# module.net
KiCad netlist of a schematic drawn in EAGLE
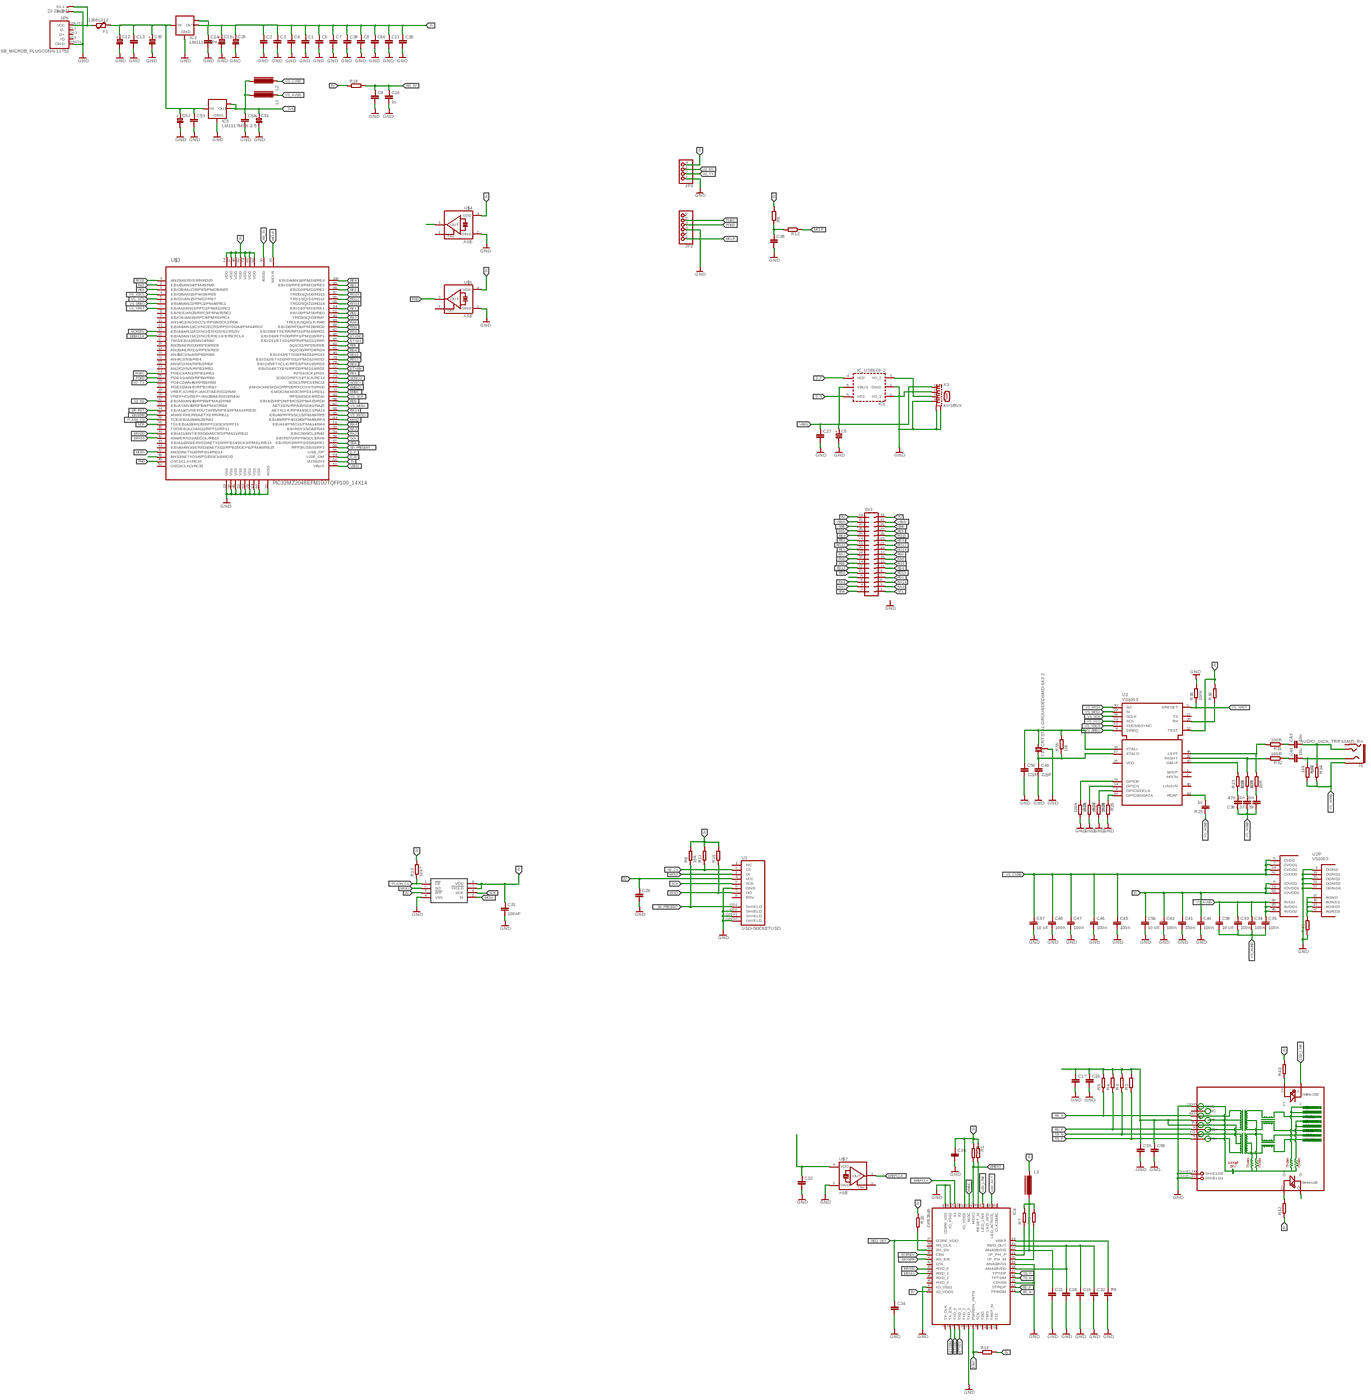
[diagram p0: schematic, sheet 1, overview]
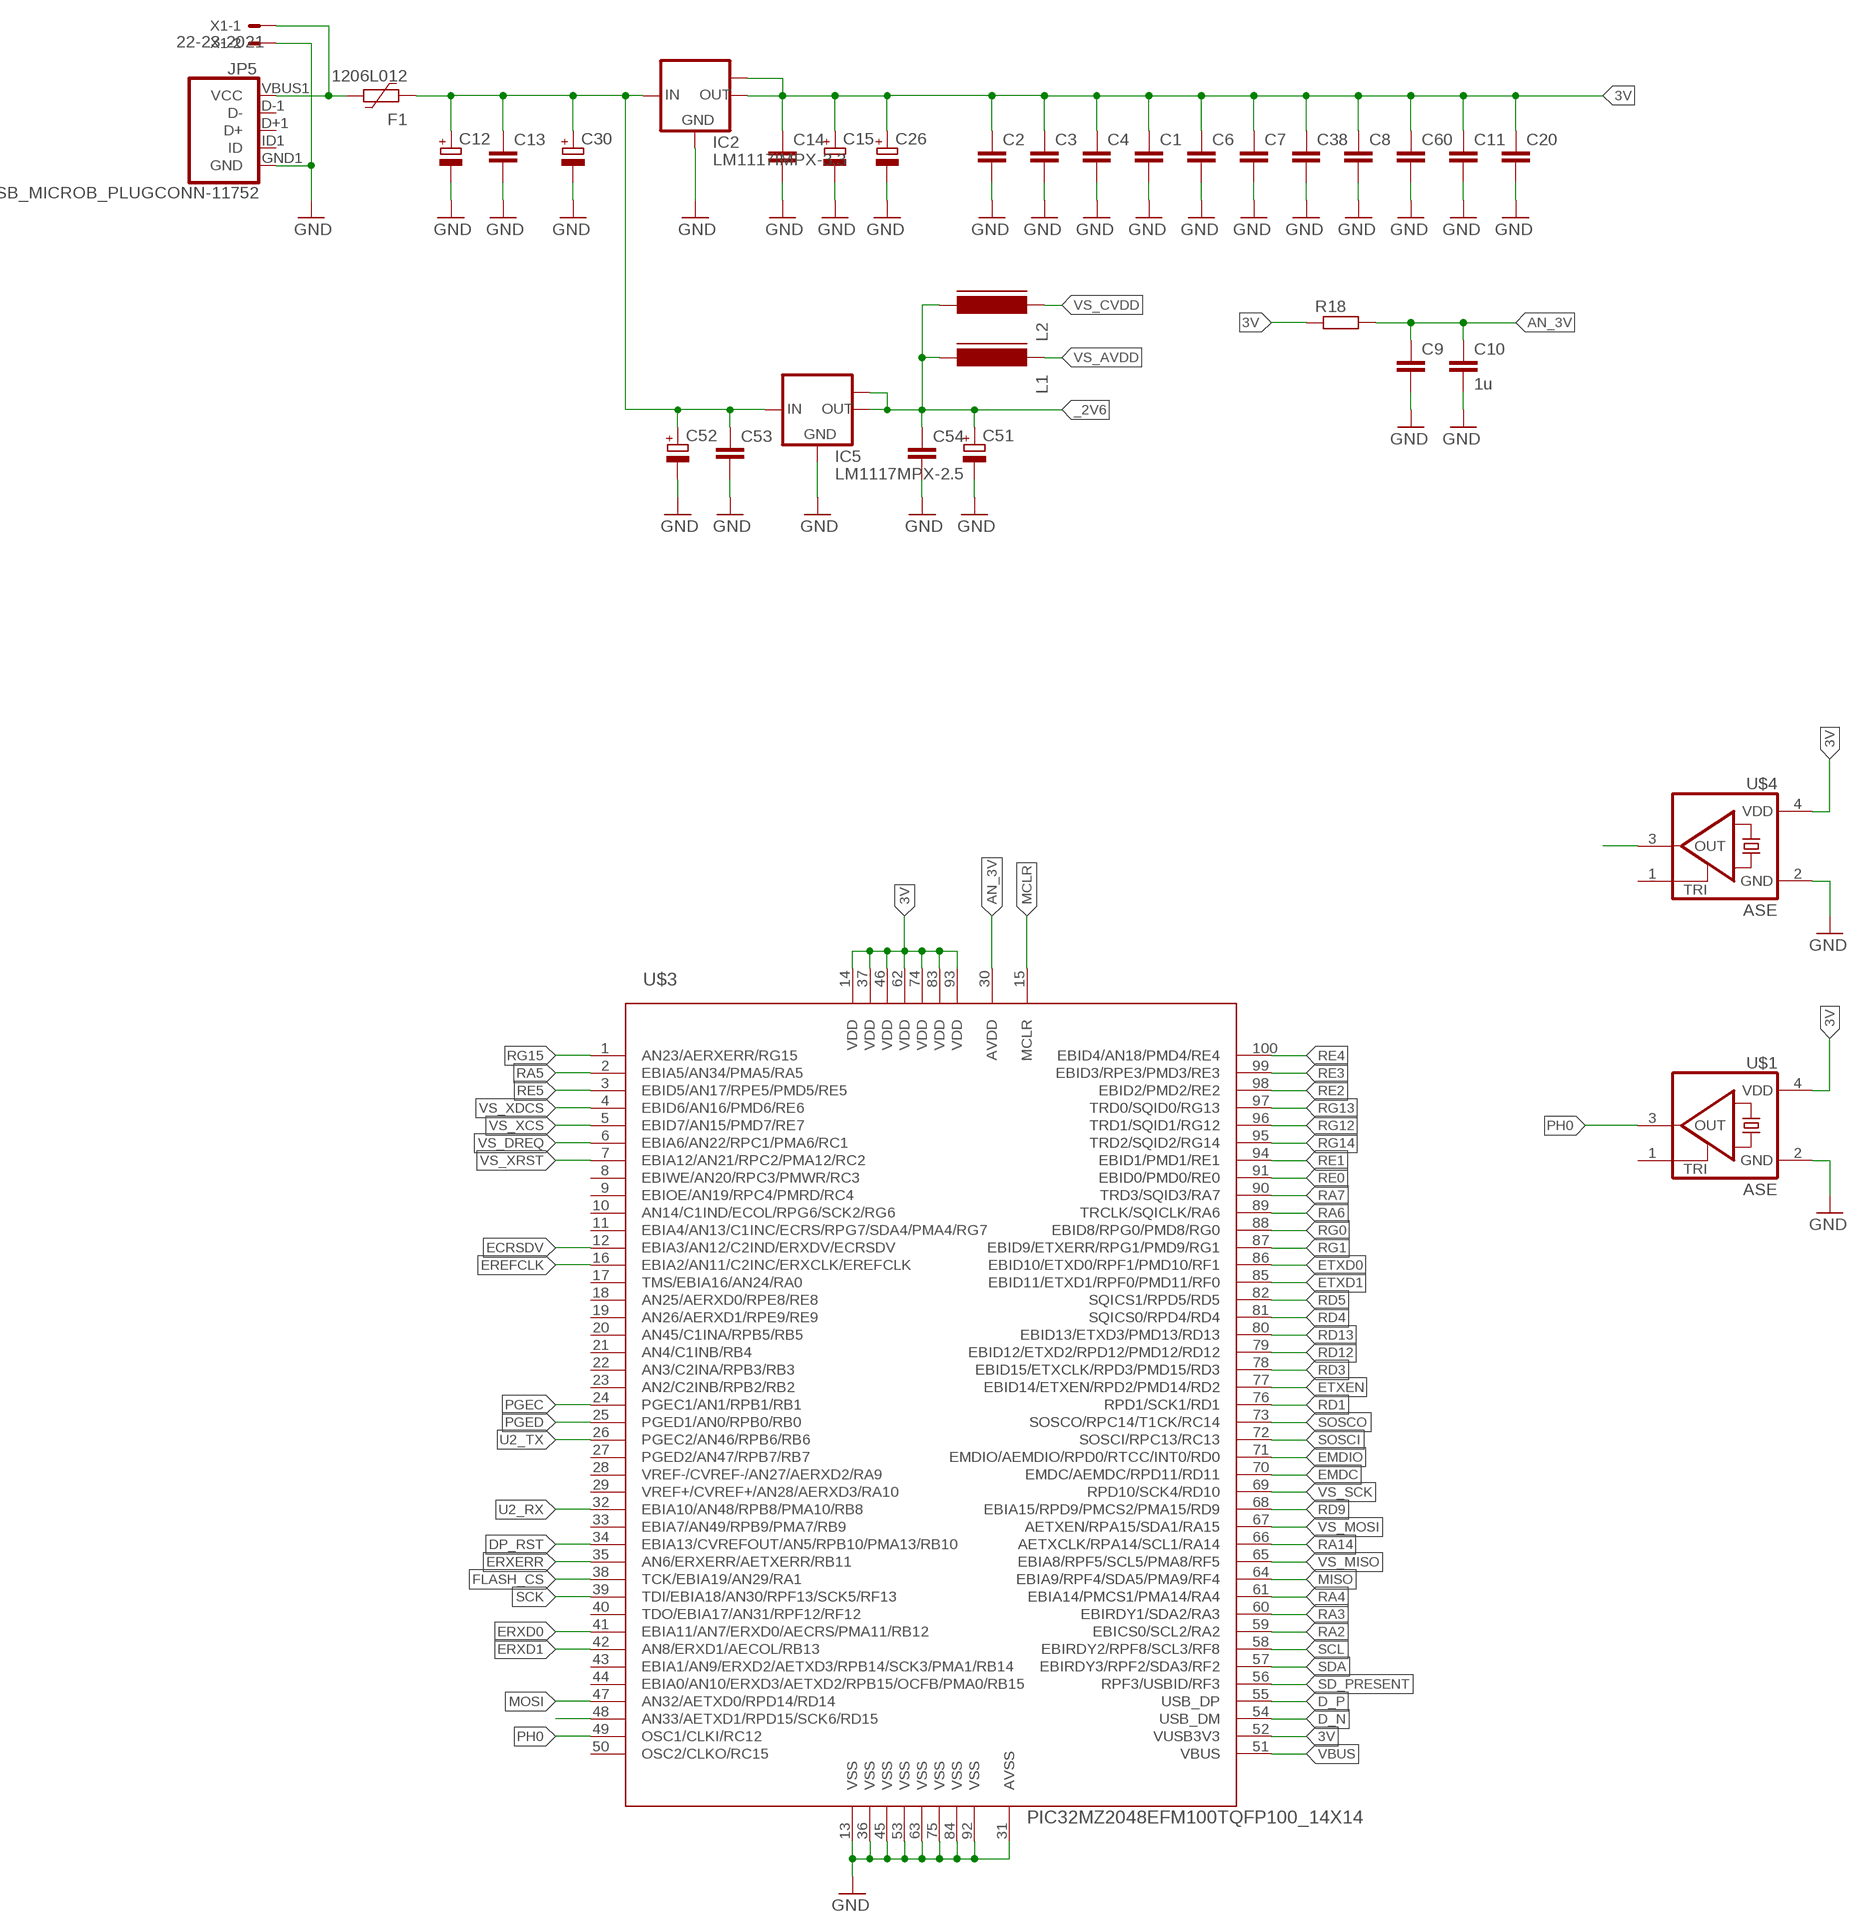
[diagram p1: schematic, sheet 1, part 1 of 4]
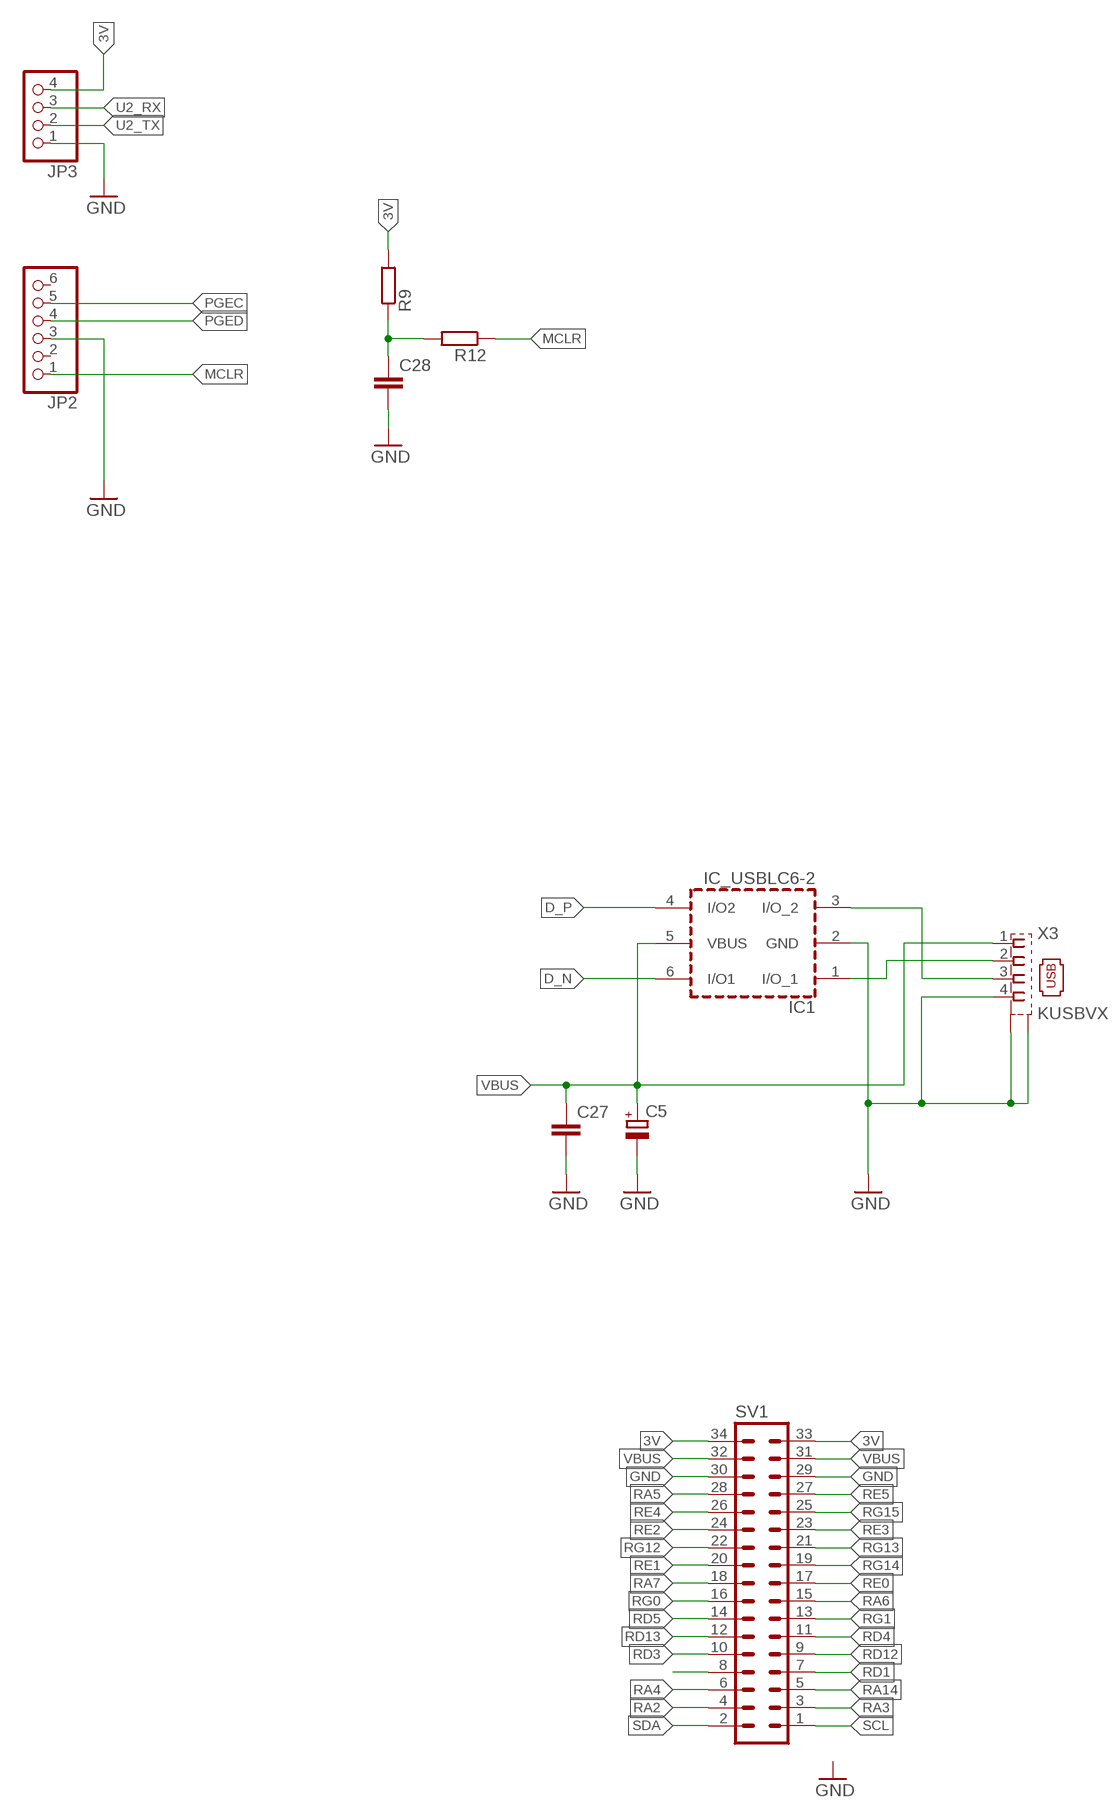
[diagram p2: schematic, sheet 1, part 2 of 4]
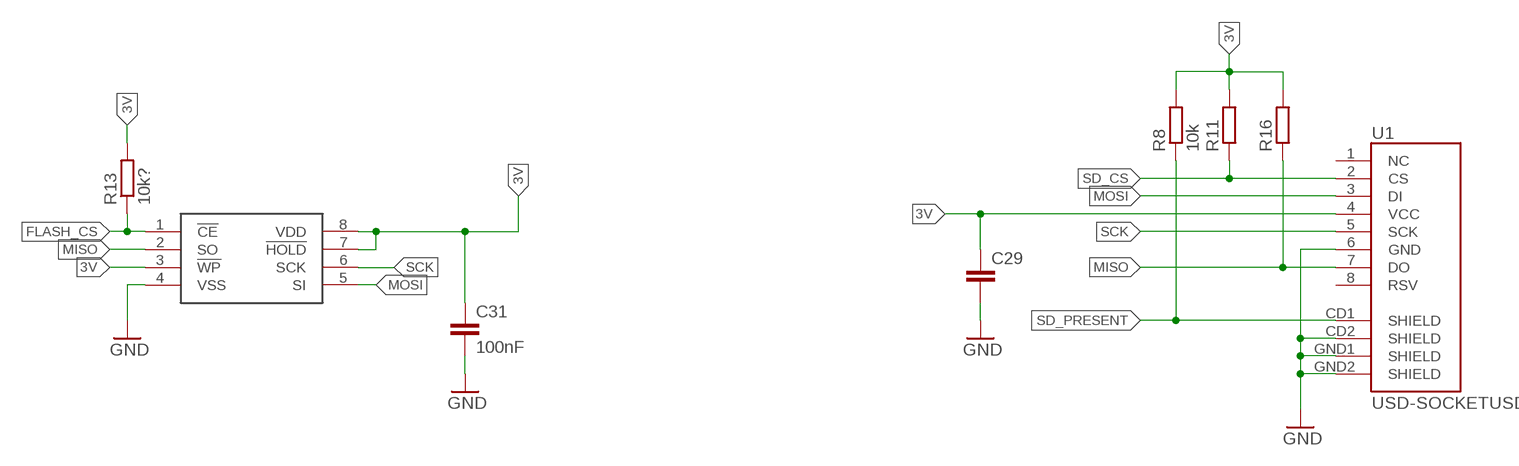
[diagram p3: schematic, sheet 1, part 3 of 4]
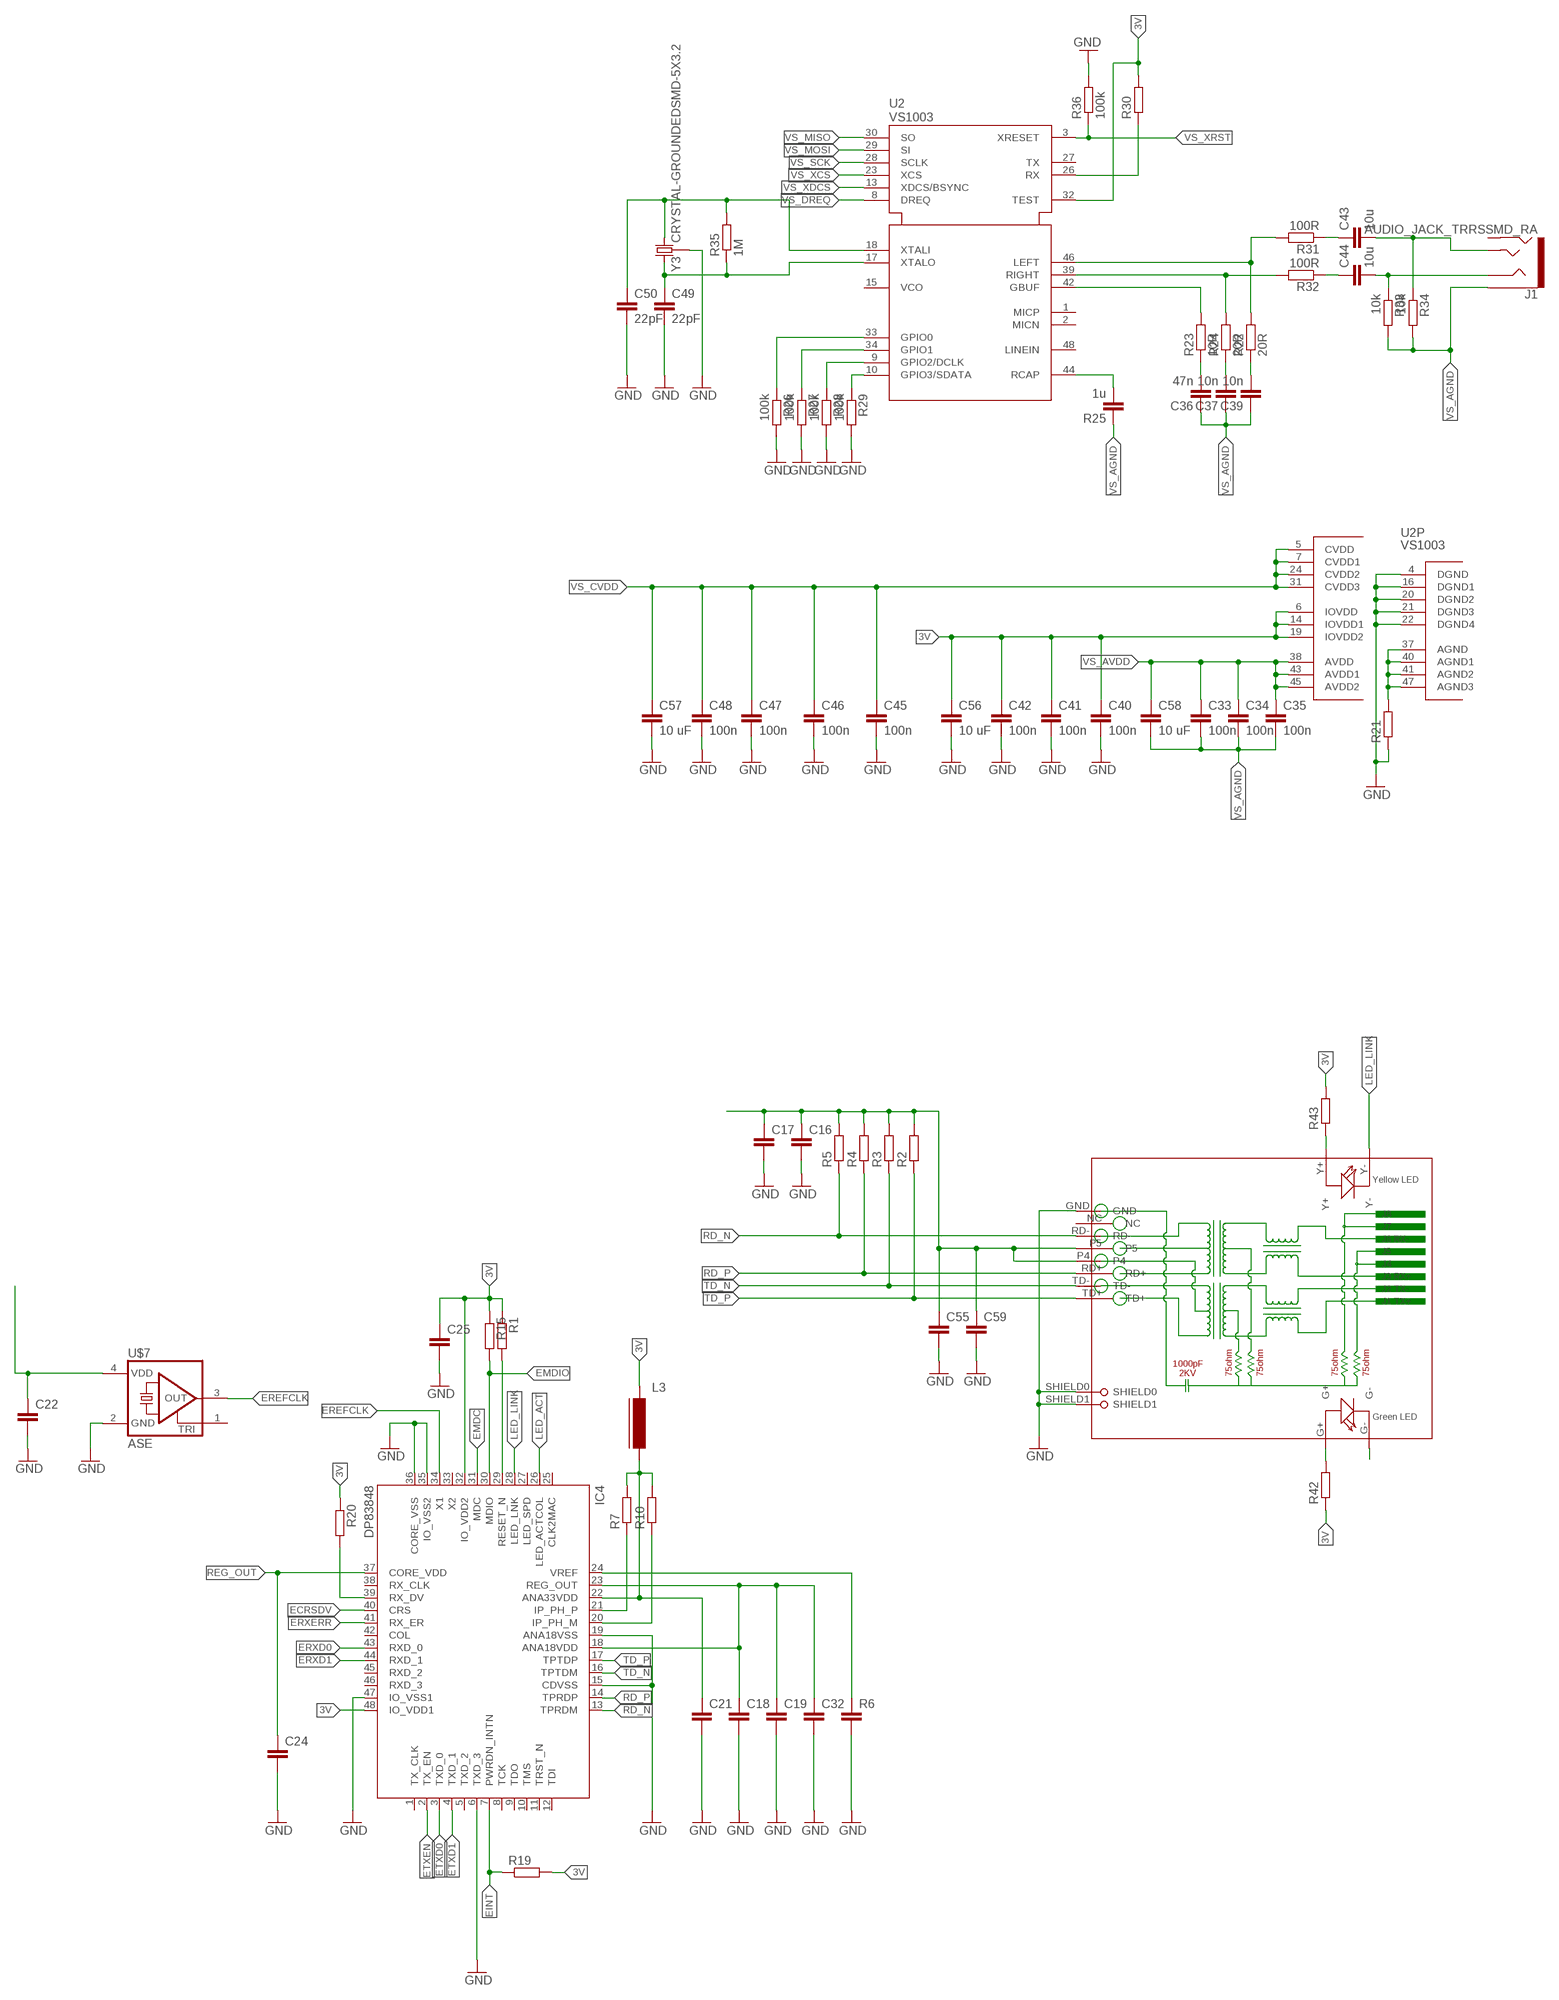
[diagram p4: schematic, sheet 1, part 4 of 4]

(export (version "E")
  (design (tool "Eeschema 10.0.6"))
  (components
    (comp (ref "C1")
      (value "C-EUC0402")
      (footprint "eagle-import:C0402")
      (libsource (lib "eagle-import") (part "C-EUC0402"))
    )
    (comp (ref "C2")
      (value "C-EUC0402")
      (footprint "eagle-import:C0402")
      (libsource (lib "eagle-import") (part "C-EUC0402"))
    )
    (comp (ref "C3")
      (value "C-EUC0402")
      (footprint "eagle-import:C0402")
      (libsource (lib "eagle-import") (part "C-EUC0402"))
    )
    (comp (ref "C4")
      (value "C-EUC0402")
      (footprint "eagle-import:C0402")
      (libsource (lib "eagle-import") (part "C-EUC0402"))
    )
    (comp (ref "C5")
      (value "CPOL-EUSMCA")
      (footprint "eagle-import:SMC_A")
      (libsource (lib "eagle-import") (part "CPOL-EUSMCA"))
    )
    (comp (ref "C6")
      (value "C-EUC0402")
      (footprint "eagle-import:C0402")
      (libsource (lib "eagle-import") (part "C-EUC0402"))
    )
    (comp (ref "C7")
      (value "C-EUC0402")
      (footprint "eagle-import:C0402")
      (libsource (lib "eagle-import") (part "C-EUC0402"))
    )
    (comp (ref "C8")
      (value "C-EUC0402")
      (footprint "eagle-import:C0402")
      (libsource (lib "eagle-import") (part "C-EUC0402"))
    )
    (comp (ref "C9")
      (value "C-EUC0402")
      (footprint "eagle-import:C0402")
      (libsource (lib "eagle-import") (part "C-EUC0402"))
    )
    (comp (ref "C10")
      (value "1u")
      (footprint "eagle-import:C0603")
      (libsource (lib "eagle-import") (part "C-EUC0603"))
    )
    (comp (ref "C11")
      (value "C-EUC0402")
      (footprint "eagle-import:C0402")
      (libsource (lib "eagle-import") (part "C-EUC0402"))
    )
    (comp (ref "C12")
      (value "CPOL-EUSMCB")
      (footprint "eagle-import:SMC_B")
      (libsource (lib "eagle-import") (part "CPOL-EUSMCB"))
    )
    (comp (ref "C13")
      (value "C-EUC0603")
      (footprint "eagle-import:C0603")
      (libsource (lib "eagle-import") (part "C-EUC0603"))
    )
    (comp (ref "C14")
      (value "C-EUC0603")
      (footprint "eagle-import:C0603")
      (libsource (lib "eagle-import") (part "C-EUC0603"))
    )
    (comp (ref "C15")
      (value "CPOL-EUSMCB")
      (footprint "eagle-import:SMC_B")
      (libsource (lib "eagle-import") (part "CPOL-EUSMCB"))
    )
    (comp (ref "C16")
      (value "C-EUC0603")
      (footprint "eagle-import:C0603")
      (libsource (lib "eagle-import") (part "C-EUC0603"))
    )
    (comp (ref "C17")
      (value "C-EUC0603")
      (footprint "eagle-import:C0603")
      (libsource (lib "eagle-import") (part "C-EUC0603"))
    )
    (comp (ref "C18")
      (value "C-EUC0402")
      (footprint "eagle-import:C0402")
      (libsource (lib "eagle-import") (part "C-EUC0402"))
    )
    (comp (ref "C19")
      (value "C-EUC0402")
      (footprint "eagle-import:C0402")
      (libsource (lib "eagle-import") (part "C-EUC0402"))
    )
    (comp (ref "C20")
      (value "C-EUC0402")
      (footprint "eagle-import:C0402")
      (libsource (lib "eagle-import") (part "C-EUC0402"))
    )
    (comp (ref "C21")
      (value "C-EUC0402")
      (footprint "eagle-import:C0402")
      (libsource (lib "eagle-import") (part "C-EUC0402"))
    )
    (comp (ref "C22")
      (value "C-EUC0402")
      (footprint "eagle-import:C0402")
      (libsource (lib "eagle-import") (part "C-EUC0402"))
    )
    (comp (ref "C24")
      (value "C-EUC0603")
      (footprint "eagle-import:C0603")
      (libsource (lib "eagle-import") (part "C-EUC0603"))
    )
    (comp (ref "C25")
      (value "C-EUC0603")
      (footprint "eagle-import:C0603")
      (libsource (lib "eagle-import") (part "C-EUC0603"))
    )
    (comp (ref "C26")
      (value "CPOL-EUSMCA")
      (footprint "eagle-import:SMC_A")
      (libsource (lib "eagle-import") (part "CPOL-EUSMCA"))
    )
    (comp (ref "C27")
      (value "C-EUC0603")
      (footprint "eagle-import:C0603")
      (libsource (lib "eagle-import") (part "C-EUC0603"))
    )
    (comp (ref "C28")
      (value "C-EUC0603")
      (footprint "eagle-import:C0603")
      (libsource (lib "eagle-import") (part "C-EUC0603"))
    )
    (comp (ref "C29")
      (value "C-EUC0603")
      (footprint "eagle-import:C0603")
      (libsource (lib "eagle-import") (part "C-EUC0603"))
    )
    (comp (ref "C30")
      (value "CPOL-EUSMCA")
      (footprint "eagle-import:SMC_A")
      (libsource (lib "eagle-import") (part "CPOL-EUSMCA"))
    )
    (comp (ref "C31")
      (value "100nF")
      (footprint "eagle-import:C0603")
      (libsource (lib "eagle-import") (part "C-EUC0603"))
    )
    (comp (ref "C32")
      (value "C-EUC0603")
      (footprint "eagle-import:C0603")
      (libsource (lib "eagle-import") (part "C-EUC0603"))
    )
    (comp (ref "C33")
      (value "100n")
      (footprint "eagle-import:C0603")
      (libsource (lib "eagle-import") (part "C-EUC0603"))
    )
    (comp (ref "C34")
      (value "100n")
      (footprint "eagle-import:C0603")
      (libsource (lib "eagle-import") (part "C-EUC0603"))
    )
    (comp (ref "C35")
      (value "100n")
      (footprint "eagle-import:C0603")
      (libsource (lib "eagle-import") (part "C-EUC0603"))
    )
    (comp (ref "C36")
      (value "47n")
      (footprint "eagle-import:C0603")
      (libsource (lib "eagle-import") (part "C-EUC0603"))
    )
    (comp (ref "C37")
      (value "10n")
      (footprint "eagle-import:C0603")
      (libsource (lib "eagle-import") (part "C-EUC0603"))
    )
    (comp (ref "C38")
      (value "C-EUC0402")
      (footprint "eagle-import:C0402")
      (libsource (lib "eagle-import") (part "C-EUC0402"))
    )
    (comp (ref "C39")
      (value "10n")
      (footprint "eagle-import:C0603")
      (libsource (lib "eagle-import") (part "C-EUC0603"))
    )
    (comp (ref "C40")
      (value "100n")
      (footprint "eagle-import:C0402")
      (libsource (lib "eagle-import") (part "C-EUC0402"))
    )
    (comp (ref "C41")
      (value "100n")
      (footprint "eagle-import:C0402")
      (libsource (lib "eagle-import") (part "C-EUC0402"))
    )
    (comp (ref "C42")
      (value "100n")
      (footprint "eagle-import:C0402")
      (libsource (lib "eagle-import") (part "C-EUC0402"))
    )
    (comp (ref "C43")
      (value "10u")
      (footprint "eagle-import:C0603")
      (libsource (lib "eagle-import") (part "C-EUC0603"))
    )
    (comp (ref "C44")
      (value "10u")
      (footprint "eagle-import:C0603")
      (libsource (lib "eagle-import") (part "C-EUC0603"))
    )
    (comp (ref "C45")
      (value "100n")
      (footprint "eagle-import:C0402")
      (libsource (lib "eagle-import") (part "C-EUC0402"))
    )
    (comp (ref "C46")
      (value "100n")
      (footprint "eagle-import:C0603")
      (libsource (lib "eagle-import") (part "C-EUC0603"))
    )
    (comp (ref "C47")
      (value "100n")
      (footprint "eagle-import:C0603")
      (libsource (lib "eagle-import") (part "C-EUC0603"))
    )
    (comp (ref "C48")
      (value "100n")
      (footprint "eagle-import:C0603")
      (libsource (lib "eagle-import") (part "C-EUC0603"))
    )
    (comp (ref "C49")
      (value "22pF")
      (footprint "eagle-import:C0603")
      (libsource (lib "eagle-import") (part "C-EUC0603"))
    )
    (comp (ref "C50")
      (value "22pF")
      (footprint "eagle-import:C0603")
      (libsource (lib "eagle-import") (part "C-EUC0603"))
    )
    (comp (ref "C51")
      (value "CPOL-EUSMCB")
      (footprint "eagle-import:SMC_B")
      (libsource (lib "eagle-import") (part "CPOL-EUSMCB"))
    )
    (comp (ref "C52")
      (value "CPOL-EUSMCB")
      (footprint "eagle-import:SMC_B")
      (libsource (lib "eagle-import") (part "CPOL-EUSMCB"))
    )
    (comp (ref "C53")
      (value "C-EUC1206")
      (footprint "eagle-import:C1206")
      (libsource (lib "eagle-import") (part "C-EUC1206"))
    )
    (comp (ref "C54")
      (value "C-EUC1206")
      (footprint "eagle-import:C1206")
      (libsource (lib "eagle-import") (part "C-EUC1206"))
    )
    (comp (ref "C55")
      (value "C-EUC0603")
      (footprint "eagle-import:C0603")
      (libsource (lib "eagle-import") (part "C-EUC0603"))
    )
    (comp (ref "C56")
      (value "10 uF")
      (footprint "eagle-import:C0603")
      (libsource (lib "eagle-import") (part "C-EUC0603"))
    )
    (comp (ref "C57")
      (value "10 uF")
      (footprint "eagle-import:C0603")
      (libsource (lib "eagle-import") (part "C-EUC0603"))
    )
    (comp (ref "C58")
      (value "10 uF")
      (footprint "eagle-import:C0603")
      (libsource (lib "eagle-import") (part "C-EUC0603"))
    )
    (comp (ref "C59")
      (value "C-EUC0603")
      (footprint "eagle-import:C0603")
      (libsource (lib "eagle-import") (part "C-EUC0603"))
    )
    (comp (ref "C60")
      (value "C-EUC0402")
      (footprint "eagle-import:C0402")
      (libsource (lib "eagle-import") (part "C-EUC0402"))
    )
    (comp (ref "F1")
      (value "1206L012")
      (footprint "eagle-import:1206L")
      (fields (field (name "MF") "Littelfuse"))
      (libsource (lib "eagle-import") (part "?1206L012"))
    )
    (comp (ref "IC1")
      (value "IC_USBLC6-2")
      (footprint "eagle-import:SOT-23-6L")
      (libsource (lib "eagle-import") (part "IC_USBLC6-2"))
    )
    (comp (ref "IC2")
      (value "LM1117IMPX-3.3")
      (footprint "eagle-import:SOT223")
      (libsource (lib "eagle-import") (part "LM1117IMPX-3.3"))
    )
    (comp (ref "IC4")
      (value "DP83848")
      (footprint "eagle-import:LQFP48")
      (fields (field (name "MPN") "DP83848VYB"))
      (libsource (lib "eagle-import") (part "DP83848"))
    )
    (comp (ref "IC5")
      (value "LM1117MPX-2.5")
      (footprint "eagle-import:SOT223")
      (libsource (lib "eagle-import") (part "LM1117MPX-2.5"))
    )
    (comp (ref "J1")
      (value "AUDIO_JACK_TRRSSMD_RA")
      (footprint "eagle-import:AUDIO_JACK_3.5MM_TRRS_SMD_RA")
      (libsource (lib "eagle-import") (part "AUDIO_JACK_TRRSSMD_RA"))
    )
    (comp (ref "JP2")
      (value "PINHD-1X6")
      (footprint "eagle-import:1X06")
      (libsource (lib "eagle-import") (part "PINHD-1X6"))
    )
    (comp (ref "JP3")
      (value "PINHD-1X4")
      (footprint "eagle-import:1X04")
      (libsource (lib "eagle-import") (part "PINHD-1X4"))
    )
    (comp (ref "JP5")
      (value "USB_MICROB_PLUGCONN-11752")
      (footprint "eagle-import:USB-B-MICRO-SMD_V03")
      (libsource (lib "eagle-import") (part "USB_MICROB_PLUGCONN-11752"))
    )
    (comp (ref "L1")
      (value "FERRITE-0805")
      (footprint "eagle-import:FB805")
      (libsource (lib "eagle-import") (part "FERRITE-0805"))
    )
    (comp (ref "L2")
      (value "FERRITE-0805")
      (footprint "eagle-import:FB805")
      (libsource (lib "eagle-import") (part "FERRITE-0805"))
    )
    (comp (ref "L3")
      (value "FERRITE-0805")
      (footprint "eagle-import:FB805")
      (libsource (lib "eagle-import") (part "FERRITE-0805"))
    )
    (comp (ref "R1")
      (value "R-EU_R0402")
      (footprint "eagle-import:R0402")
      (libsource (lib "eagle-import") (part "R-EU_R0402"))
    )
    (comp (ref "R2")
      (value "R-EU_R0603")
      (footprint "eagle-import:R0603")
      (libsource (lib "eagle-import") (part "R-EU_R0603"))
    )
    (comp (ref "R3")
      (value "R-EU_R0603")
      (footprint "eagle-import:R0603")
      (libsource (lib "eagle-import") (part "R-EU_R0603"))
    )
    (comp (ref "R4")
      (value "R-EU_R0603")
      (footprint "eagle-import:R0603")
      (libsource (lib "eagle-import") (part "R-EU_R0603"))
    )
    (comp (ref "R5")
      (value "R-EU_R0603")
      (footprint "eagle-import:R0603")
      (libsource (lib "eagle-import") (part "R-EU_R0603"))
    )
    (comp (ref "R6")
      (value "C-EUC0603")
      (footprint "eagle-import:C0603")
      (libsource (lib "eagle-import") (part "C-EUC0603"))
    )
    (comp (ref "R7")
      (value "R-EU_R0402")
      (footprint "eagle-import:R0402")
      (libsource (lib "eagle-import") (part "R-EU_R0402"))
    )
    (comp (ref "R8")
      (value "10k")
      (footprint "eagle-import:R0603")
      (libsource (lib "eagle-import") (part "R-EU_R0603"))
    )
    (comp (ref "R9")
      (value "R-EU_R0603")
      (footprint "eagle-import:R0603")
      (libsource (lib "eagle-import") (part "R-EU_R0603"))
    )
    (comp (ref "R10")
      (value "R-EU_R0402")
      (footprint "eagle-import:R0402")
      (libsource (lib "eagle-import") (part "R-EU_R0402"))
    )
    (comp (ref "R11")
      (value "R-EU_R0603")
      (footprint "eagle-import:R0603")
      (libsource (lib "eagle-import") (part "R-EU_R0603"))
    )
    (comp (ref "R12")
      (value "R-EU_R0402")
      (footprint "eagle-import:R0402")
      (libsource (lib "eagle-import") (part "R-EU_R0402"))
    )
    (comp (ref "R13")
      (value "10k?")
      (footprint "eagle-import:R0603")
      (libsource (lib "eagle-import") (part "R-EU_R0603"))
    )
    (comp (ref "R15")
      (value "R-EU_R0603")
      (footprint "eagle-import:R0603")
      (libsource (lib "eagle-import") (part "R-EU_R0603"))
    )
    (comp (ref "R16")
      (value "R-EU_R0603")
      (footprint "eagle-import:R0603")
      (libsource (lib "eagle-import") (part "R-EU_R0603"))
    )
    (comp (ref "R18")
      (value "R-EU_R0805")
      (footprint "eagle-import:R0805")
      (libsource (lib "eagle-import") (part "R-EU_R0805"))
    )
    (comp (ref "R19")
      (value "R-EU_R0402")
      (footprint "eagle-import:R0402")
      (libsource (lib "eagle-import") (part "R-EU_R0402"))
    )
    (comp (ref "R20")
      (value "R-EU_R0603")
      (footprint "eagle-import:R0603")
      (libsource (lib "eagle-import") (part "R-EU_R0603"))
    )
    (comp (ref "R21")
      (value "R-EU_R0603")
      (footprint "eagle-import:R0603")
      (libsource (lib "eagle-import") (part "R-EU_R0603"))
    )
    (comp (ref "R22")
      (value "20R")
      (footprint "eagle-import:R0603")
      (libsource (lib "eagle-import") (part "R-EU_R0603"))
    )
    (comp (ref "R23")
      (value "10R")
      (footprint "eagle-import:R0603")
      (libsource (lib "eagle-import") (part "R-EU_R0603"))
    )
    (comp (ref "R24")
      (value "20R")
      (footprint "eagle-import:R0603")
      (libsource (lib "eagle-import") (part "R-EU_R0603"))
    )
    (comp (ref "R25")
      (value "1u")
      (footprint "eagle-import:C0603")
      (libsource (lib "eagle-import") (part "C-EUC0603"))
    )
    (comp (ref "R26")
      (value "100k")
      (footprint "eagle-import:R0402")
      (libsource (lib "eagle-import") (part "R-EU_R0402"))
    )
    (comp (ref "R27")
      (value "100k")
      (footprint "eagle-import:R0402")
      (libsource (lib "eagle-import") (part "R-EU_R0402"))
    )
    (comp (ref "R28")
      (value "100k")
      (footprint "eagle-import:R0402")
      (libsource (lib "eagle-import") (part "R-EU_R0402"))
    )
    (comp (ref "R29")
      (value "100k")
      (footprint "eagle-import:R0402")
      (libsource (lib "eagle-import") (part "R-EU_R0402"))
    )
    (comp (ref "R30")
      (value "R-EU_0204/7")
      (footprint "eagle-import:0204_7")
      (libsource (lib "eagle-import") (part "R-EU_0204/7"))
    )
    (comp (ref "R31")
      (value "100R")
      (footprint "eagle-import:R0603")
      (libsource (lib "eagle-import") (part "R-EU_R0603"))
    )
    (comp (ref "R32")
      (value "100R")
      (footprint "eagle-import:R0603")
      (libsource (lib "eagle-import") (part "R-EU_R0603"))
    )
    (comp (ref "R33")
      (value "10k")
      (footprint "eagle-import:R0603")
      (libsource (lib "eagle-import") (part "R-EU_R0603"))
    )
    (comp (ref "R34")
      (value "10k")
      (footprint "eagle-import:R0603")
      (libsource (lib "eagle-import") (part "R-EU_R0603"))
    )
    (comp (ref "R35")
      (value "1M")
      (footprint "eagle-import:R0603")
      (libsource (lib "eagle-import") (part "R-EU_R0603"))
    )
    (comp (ref "R36")
      (value "100k")
      (footprint "eagle-import:R0603")
      (libsource (lib "eagle-import") (part "R-EU_R0603"))
    )
    (comp (ref "R42")
      (value "R-EU_R0603")
      (footprint "eagle-import:R0603")
      (libsource (lib "eagle-import") (part "R-EU_R0603"))
    )
    (comp (ref "R43")
      (value "R-EU_R0603")
      (footprint "eagle-import:R0603")
      (libsource (lib "eagle-import") (part "R-EU_R0603"))
    )
    (comp (ref "RJ1")
      (value "HR911105A")
      (footprint "eagle-import:HR911105A")
      (libsource (lib "eagle-import") (part "HR911105A"))
    )
    (comp (ref "SV1")
      (value "ML34L")
      (footprint "eagle-import:ML34L")
      (libsource (lib "eagle-import") (part "ML34L"))
    )
    (comp (ref "U$1")
      (value "ASE")
      (footprint "eagle-import:ASE")
      (libsource (lib "eagle-import") (part "ASE"))
    )
    (comp (ref "U$2")
      (value "SST25VF016BSO8M")
      (footprint "eagle-import:SO-08M")
      (libsource (lib "eagle-import") (part "SST25VF016BSO8M"))
    )
    (comp (ref "U$3")
      (value "PIC32MZ2048EFM100TQFP100_14X14")
      (footprint "eagle-import:TQFP100_14X14")
      (libsource (lib "eagle-import") (part "PIC32MZ2048EFM100TQFP100_14X14"))
    )
    (comp (ref "U$4")
      (value "ASE")
      (footprint "eagle-import:ASE")
      (libsource (lib "eagle-import") (part "ASE"))
    )
    (comp (ref "U$7")
      (value "ASE")
      (footprint "eagle-import:ASE")
      (libsource (lib "eagle-import") (part "ASE"))
    )
    (comp (ref "U1")
      (value "USD-SOCKETUSD")
      (footprint "eagle-import:USD-SOCKET-PP")
      (libsource (lib "eagle-import") (part "USD-SOCKETUSD"))
    )
    (comp (ref "U2")
      (value "VS1003")
      (footprint "eagle-import:LQFP48")
      (libsource (lib "eagle-import") (part "VS1003"))
    )
    (comp (ref "X1")
      (value "22-23-2021")
      (footprint "eagle-import:22-23-2021")
      (fields (field (name "MF") "MOLEX"))
      (libsource (lib "eagle-import") (part "22-23-2021"))
    )
    (comp (ref "X3")
      (value "KUSBVX")
      (footprint "eagle-import:KUSBVX")
      (libsource (lib "eagle-import") (part "KUSBVX"))
    )
    (comp (ref "Y3")
      (value "CRYSTAL-GROUNDEDSMD-5X3.2")
      (footprint "eagle-import:CRYSTAL-SMD-5X3.2-4PAD")
      (libsource (lib "eagle-import") (part "CRYSTAL-GROUNDEDSMD-5X3.2"))
    )
  )
  (nets
    (net (code "1") (name "/A3V") (class "Default")
      (node (ref "C16") (pin "1") (pinfunction "1_1") (pintype "passive"))
      (node (ref "C17") (pin "1") (pinfunction "1_1") (pintype "passive"))
      (node (ref "C21") (pin "1") (pinfunction "1_1") (pintype "passive"))
      (node (ref "C55") (pin "1") (pinfunction "1_1") (pintype "passive"))
      (node (ref "C59") (pin "1") (pinfunction "1_1") (pintype "passive"))
      (node (ref "IC4") (pin "22") (pinfunction "ANA33VDD_22") (pintype "power_in"))
      (node (ref "L3") (pin "2") (pinfunction "2_2") (pintype "passive"))
      (node (ref "R10") (pin "2") (pinfunction "2_2") (pintype "passive"))
      (node (ref "R2") (pin "2") (pinfunction "2_2") (pintype "passive"))
      (node (ref "R3") (pin "2") (pinfunction "2_2") (pintype "passive"))
      (node (ref "R4") (pin "2") (pinfunction "2_2") (pintype "passive"))
      (node (ref "R5") (pin "2") (pinfunction "2_2") (pintype "passive"))
      (node (ref "R7") (pin "2") (pinfunction "2_2") (pintype "passive"))
      (node (ref "RJ1") (pin "P4") (pinfunction "P4_P4") (pintype "bidirectional"))
      (node (ref "RJ1") (pin "P5") (pinfunction "P5_P5") (pintype "bidirectional"))
    )
    (net (code "2") (name "3V") (class "Default")
      (node (ref "C1") (pin "1") (pinfunction "1_1") (pintype "passive"))
      (node (ref "C11") (pin "1") (pinfunction "1_1") (pintype "passive"))
      (node (ref "C14") (pin "1") (pinfunction "1_1") (pintype "passive"))
      (node (ref "C15") (pin "+") (pinfunction "+_+") (pintype "passive"))
      (node (ref "C2") (pin "1") (pinfunction "1_1") (pintype "passive"))
      (node (ref "C20") (pin "1") (pinfunction "1_1") (pintype "passive"))
      (node (ref "C22") (pin "1") (pinfunction "1_1") (pintype "passive"))
      (node (ref "C25") (pin "1") (pinfunction "1_1") (pintype "passive"))
      (node (ref "C26") (pin "+") (pinfunction "+_+") (pintype "passive"))
      (node (ref "C29") (pin "1") (pinfunction "1_1") (pintype "passive"))
      (node (ref "C3") (pin "1") (pinfunction "1_1") (pintype "passive"))
      (node (ref "C31") (pin "1") (pinfunction "1_1") (pintype "passive"))
      (node (ref "C38") (pin "1") (pinfunction "1_1") (pintype "passive"))
      (node (ref "C4") (pin "1") (pinfunction "1_1") (pintype "passive"))
      (node (ref "C40") (pin "1") (pinfunction "1_1") (pintype "passive"))
      (node (ref "C41") (pin "1") (pinfunction "1_1") (pintype "passive"))
      (node (ref "C42") (pin "1") (pinfunction "1_1") (pintype "passive"))
      (node (ref "C56") (pin "1") (pinfunction "1_1") (pintype "passive"))
      (node (ref "C6") (pin "1") (pinfunction "1_1") (pintype "passive"))
      (node (ref "C60") (pin "1") (pinfunction "1_1") (pintype "passive"))
      (node (ref "C7") (pin "1") (pinfunction "1_1") (pintype "passive"))
      (node (ref "C8") (pin "1") (pinfunction "1_1") (pintype "passive"))
      (node (ref "IC2") (pin "2") (pinfunction "OUT_2") (pintype "passive"))
      (node (ref "IC2") (pin "TAB") (pinfunction "OUT1_TAB") (pintype "passive"))
      (node (ref "IC4") (pin "32") (pinfunction "IO_VDD2_32") (pintype "power_in"))
      (node (ref "IC4") (pin "48") (pinfunction "IO_VDD1_48") (pintype "power_in"))
      (node (ref "JP3") (pin "4") (pinfunction "4_4") (pintype "passive"))
      (node (ref "L3") (pin "1") (pinfunction "1_1") (pintype "passive"))
      (node (ref "R1") (pin "1") (pinfunction "1_1") (pintype "passive"))
      (node (ref "R11") (pin "2") (pinfunction "2_2") (pintype "passive"))
      (node (ref "R13") (pin "2") (pinfunction "2_2") (pintype "passive"))
      (node (ref "R15") (pin "1") (pinfunction "1_1") (pintype "passive"))
      (node (ref "R16") (pin "2") (pinfunction "2_2") (pintype "passive"))
      (node (ref "R18") (pin "1") (pinfunction "1_1") (pintype "passive"))
      (node (ref "R19") (pin "2") (pinfunction "2_2") (pintype "passive"))
      (node (ref "R20") (pin "1") (pinfunction "1_1") (pintype "passive"))
      (node (ref "R30") (pin "2") (pinfunction "2_2") (pintype "passive"))
      (node (ref "R42") (pin "1") (pinfunction "1_1") (pintype "passive"))
      (node (ref "R43") (pin "2") (pinfunction "2_2") (pintype "passive"))
      (node (ref "R8") (pin "2") (pinfunction "2_2") (pintype "passive"))
      (node (ref "R9") (pin "2") (pinfunction "2_2") (pintype "passive"))
      (node (ref "SV1") (pin "33") (pinfunction "33_33") (pintype "passive"))
      (node (ref "SV1") (pin "34") (pinfunction "34_34") (pintype "passive"))
      (node (ref "U$1") (pin "4") (pinfunction "VDD_4") (pintype "power_in"))
      (node (ref "U$2") (pin "3") (pinfunction "~{WP}_3") (pintype "bidirectional"))
      (node (ref "U$2") (pin "7") (pinfunction "~{HOLD}_7") (pintype "bidirectional"))
      (node (ref "U$2") (pin "8") (pinfunction "VDD_8") (pintype "bidirectional"))
      (node (ref "U$3") (pin "14") (pinfunction "VDD_14") (pintype "bidirectional"))
      (node (ref "U$3") (pin "37") (pinfunction "VDD_37") (pintype "bidirectional"))
      (node (ref "U$3") (pin "46") (pinfunction "VDD_46") (pintype "bidirectional"))
      (node (ref "U$3") (pin "52") (pinfunction "VUSB3V3_52") (pintype "bidirectional"))
      (node (ref "U$3") (pin "62") (pinfunction "VDD_62") (pintype "bidirectional"))
      (node (ref "U$3") (pin "74") (pinfunction "VDD_74") (pintype "bidirectional"))
      (node (ref "U$3") (pin "83") (pinfunction "VDD_83") (pintype "bidirectional"))
      (node (ref "U$3") (pin "93") (pinfunction "VDD_93") (pintype "bidirectional"))
      (node (ref "U$4") (pin "4") (pinfunction "VDD_4") (pintype "power_in"))
      (node (ref "U$7") (pin "4") (pinfunction "VDD_4") (pintype "power_in"))
      (node (ref "U1") (pin "4") (pinfunction "VCC_4") (pintype "bidirectional"))
      (node (ref "U2") (pin "14") (pinfunction "IOVDD1_14") (pintype "power_in"))
      (node (ref "U2") (pin "19") (pinfunction "IOVDD2_19") (pintype "power_in"))
      (node (ref "U2") (pin "32") (pinfunction "TEST_32") (pintype "bidirectional"))
      (node (ref "U2") (pin "6") (pinfunction "IOVDD_6") (pintype "power_in"))
    )
    (net (code "3") (name "AN_3V") (class "Default")
      (node (ref "C10") (pin "1") (pinfunction "1_1") (pintype "passive"))
      (node (ref "C9") (pin "1") (pinfunction "1_1") (pintype "passive"))
      (node (ref "R18") (pin "2") (pinfunction "2_2") (pintype "passive"))
      (node (ref "U$3") (pin "30") (pinfunction "AVDD_30") (pintype "bidirectional"))
    )
    (net (code "4") (name "DP_RST") (class "Default")
      (node (ref "IC4") (pin "29") (pinfunction "RESET_N_29") (pintype "input"))
      (node (ref "R1") (pin "2") (pinfunction "2_2") (pintype "passive"))
      (node (ref "U$3") (pin "34") (pinfunction "EBIA13/CVREFOUT/AN5/RPB10/PMA13/RB10_34") (pintype "bidirectional"))
    )
    (net (code "5") (name "D_N") (class "Default")
      (node (ref "IC1") (pin "6") (pinfunction "I/O1_6") (pintype "bidirectional"))
      (node (ref "U$3") (pin "54") (pinfunction "USB_DM_54") (pintype "bidirectional"))
    )
    (net (code "6") (name "D_P") (class "Default")
      (node (ref "IC1") (pin "4") (pinfunction "I/O2_4") (pintype "bidirectional"))
      (node (ref "U$3") (pin "55") (pinfunction "USB_DP_55") (pintype "bidirectional"))
    )
    (net (code "7") (name "ECRSDV") (class "Default")
      (node (ref "IC4") (pin "40") (pinfunction "CRS_40") (pintype "bidirectional"))
      (node (ref "U$3") (pin "12") (pinfunction "EBIA3/AN12/C2IND/ERXDV/ECRSDV_12") (pintype "bidirectional"))
    )
    (net (code "8") (name "EINT") (class "Default")
      (node (ref "IC4") (pin "7") (pinfunction "PWRDN_INTN_7") (pintype "bidirectional"))
      (node (ref "R19") (pin "1") (pinfunction "1_1") (pintype "passive"))
    )
    (net (code "9") (name "EMDC") (class "Default")
      (node (ref "IC4") (pin "31") (pinfunction "MDC_31") (pintype "input"))
      (node (ref "U$3") (pin "70") (pinfunction "EMDC/AEMDC/RPD11/RD11_70") (pintype "bidirectional"))
    )
    (net (code "10") (name "EMDIO") (class "Default")
      (node (ref "IC4") (pin "30") (pinfunction "MDIO_30") (pintype "bidirectional"))
      (node (ref "R15") (pin "2") (pinfunction "2_2") (pintype "passive"))
      (node (ref "U$3") (pin "71") (pinfunction "EMDIO/AEMDIO/RPD0/RTCC/INT0/RD0_71") (pintype "bidirectional"))
    )
    (net (code "11") (name "EREFCLK") (class "Default")
      (node (ref "IC4") (pin "34") (pinfunction "X1_34") (pintype "input"))
      (node (ref "U$3") (pin "16") (pinfunction "EBIA2/AN11/C2INC/ERXCLK/EREFCLK_16") (pintype "bidirectional"))
      (node (ref "U$7") (pin "3") (pinfunction "OUT_3") (pintype "output"))
    )
    (net (code "12") (name "ERXD0") (class "Default")
      (node (ref "IC4") (pin "43") (pinfunction "RXD_0_43") (pintype "bidirectional"))
      (node (ref "U$3") (pin "41") (pinfunction "EBIA11/AN7/ERXD0/AECRS/PMA11/RB12_41") (pintype "bidirectional"))
    )
    (net (code "13") (name "ERXD1") (class "Default")
      (node (ref "IC4") (pin "44") (pinfunction "RXD_1_44") (pintype "bidirectional"))
      (node (ref "U$3") (pin "42") (pinfunction "AN8/ERXD1/AECOL/RB13_42") (pintype "bidirectional"))
    )
    (net (code "14") (name "ERXERR") (class "Default")
      (node (ref "IC4") (pin "41") (pinfunction "RX_ER_41") (pintype "bidirectional"))
      (node (ref "U$3") (pin "35") (pinfunction "AN6/ERXERR/AETXERR/RB11_35") (pintype "bidirectional"))
    )
    (net (code "15") (name "ETXD0") (class "Default")
      (node (ref "IC4") (pin "3") (pinfunction "TXD_0_3") (pintype "bidirectional"))
      (node (ref "U$3") (pin "86") (pinfunction "EBID10/ETXD0/RPF1/PMD10/RF1_86") (pintype "bidirectional"))
    )
    (net (code "16") (name "ETXD1") (class "Default")
      (node (ref "IC4") (pin "4") (pinfunction "TXD_1_4") (pintype "bidirectional"))
      (node (ref "U$3") (pin "85") (pinfunction "EBID11/ETXD1/RPF0/PMD11/RF0_85") (pintype "bidirectional"))
    )
    (net (code "17") (name "ETXEN") (class "Default")
      (node (ref "IC4") (pin "2") (pinfunction "TX_EN_2") (pintype "bidirectional"))
      (node (ref "U$3") (pin "77") (pinfunction "EBID14/ETXEN/RPD2/PMD14/RD2_77") (pintype "bidirectional"))
    )
    (net (code "18") (name "FLASH_CS") (class "Default")
      (node (ref "R13") (pin "1") (pinfunction "1_1") (pintype "passive"))
      (node (ref "U$2") (pin "1") (pinfunction "~{CE}_1") (pintype "bidirectional"))
      (node (ref "U$3") (pin "38") (pinfunction "TCK/EBIA19/AN29/RA1_38") (pintype "bidirectional"))
    )
    (net (code "19") (name "GND") (class "Default")
      (node (ref "C1") (pin "2") (pinfunction "2_2") (pintype "passive"))
      (node (ref "C10") (pin "2") (pinfunction "2_2") (pintype "passive"))
      (node (ref "C11") (pin "2") (pinfunction "2_2") (pintype "passive"))
      (node (ref "C12") (pin "-") (pinfunction "-_-") (pintype "passive"))
      (node (ref "C13") (pin "2") (pinfunction "2_2") (pintype "passive"))
      (node (ref "C14") (pin "2") (pinfunction "2_2") (pintype "passive"))
      (node (ref "C15") (pin "-") (pinfunction "-_-") (pintype "passive"))
      (node (ref "C16") (pin "2") (pinfunction "2_2") (pintype "passive"))
      (node (ref "C17") (pin "2") (pinfunction "2_2") (pintype "passive"))
      (node (ref "C18") (pin "2") (pinfunction "2_2") (pintype "passive"))
      (node (ref "C19") (pin "2") (pinfunction "2_2") (pintype "passive"))
      (node (ref "C2") (pin "2") (pinfunction "2_2") (pintype "passive"))
      (node (ref "C20") (pin "2") (pinfunction "2_2") (pintype "passive"))
      (node (ref "C21") (pin "2") (pinfunction "2_2") (pintype "passive"))
      (node (ref "C22") (pin "2") (pinfunction "2_2") (pintype "passive"))
      (node (ref "C24") (pin "2") (pinfunction "2_2") (pintype "passive"))
      (node (ref "C25") (pin "2") (pinfunction "2_2") (pintype "passive"))
      (node (ref "C26") (pin "-") (pinfunction "-_-") (pintype "passive"))
      (node (ref "C27") (pin "2") (pinfunction "2_2") (pintype "passive"))
      (node (ref "C28") (pin "2") (pinfunction "2_2") (pintype "passive"))
      (node (ref "C29") (pin "2") (pinfunction "2_2") (pintype "passive"))
      (node (ref "C3") (pin "2") (pinfunction "2_2") (pintype "passive"))
      (node (ref "C30") (pin "-") (pinfunction "-_-") (pintype "passive"))
      (node (ref "C31") (pin "2") (pinfunction "2_2") (pintype "passive"))
      (node (ref "C32") (pin "2") (pinfunction "2_2") (pintype "passive"))
      (node (ref "C38") (pin "2") (pinfunction "2_2") (pintype "passive"))
      (node (ref "C4") (pin "2") (pinfunction "2_2") (pintype "passive"))
      (node (ref "C40") (pin "2") (pinfunction "2_2") (pintype "passive"))
      (node (ref "C41") (pin "2") (pinfunction "2_2") (pintype "passive"))
      (node (ref "C42") (pin "2") (pinfunction "2_2") (pintype "passive"))
      (node (ref "C45") (pin "2") (pinfunction "2_2") (pintype "passive"))
      (node (ref "C46") (pin "2") (pinfunction "2_2") (pintype "passive"))
      (node (ref "C47") (pin "2") (pinfunction "2_2") (pintype "passive"))
      (node (ref "C48") (pin "2") (pinfunction "2_2") (pintype "passive"))
      (node (ref "C49") (pin "2") (pinfunction "2_2") (pintype "passive"))
      (node (ref "C5") (pin "-") (pinfunction "-_-") (pintype "passive"))
      (node (ref "C50") (pin "2") (pinfunction "2_2") (pintype "passive"))
      (node (ref "C51") (pin "-") (pinfunction "-_-") (pintype "passive"))
      (node (ref "C52") (pin "-") (pinfunction "-_-") (pintype "passive"))
      (node (ref "C53") (pin "2") (pinfunction "2_2") (pintype "passive"))
      (node (ref "C54") (pin "2") (pinfunction "2_2") (pintype "passive"))
      (node (ref "C55") (pin "2") (pinfunction "2_2") (pintype "passive"))
      (node (ref "C56") (pin "2") (pinfunction "2_2") (pintype "passive"))
      (node (ref "C57") (pin "2") (pinfunction "2_2") (pintype "passive"))
      (node (ref "C59") (pin "2") (pinfunction "2_2") (pintype "passive"))
      (node (ref "C6") (pin "2") (pinfunction "2_2") (pintype "passive"))
      (node (ref "C60") (pin "2") (pinfunction "2_2") (pintype "passive"))
      (node (ref "C7") (pin "2") (pinfunction "2_2") (pintype "passive"))
      (node (ref "C8") (pin "2") (pinfunction "2_2") (pintype "passive"))
      (node (ref "C9") (pin "2") (pinfunction "2_2") (pintype "passive"))
      (node (ref "IC1") (pin "2") (pinfunction "GND_2") (pintype "bidirectional"))
      (node (ref "IC2") (pin "1") (pinfunction "GND_1") (pintype "input"))
      (node (ref "IC4") (pin "15") (pinfunction "CDVSS_15") (pintype "power_in"))
      (node (ref "IC4") (pin "19") (pinfunction "ANA18VSS_19") (pintype "power_in"))
      (node (ref "IC4") (pin "35") (pinfunction "IO_VSS2_35") (pintype "power_in"))
      (node (ref "IC4") (pin "36") (pinfunction "CORE_VSS_36") (pintype "power_in"))
      (node (ref "IC4") (pin "47") (pinfunction "IO_VSS1_47") (pintype "power_in"))
      (node (ref "IC4") (pin "6") (pinfunction "TXD_3_6") (pintype "bidirectional"))
      (node (ref "IC5") (pin "1") (pinfunction "GND_1") (pintype "input"))
      (node (ref "JP2") (pin "3") (pinfunction "3_3") (pintype "passive"))
      (node (ref "JP3") (pin "1") (pinfunction "1_1") (pintype "passive"))
      (node (ref "JP5") (pin "GND1") (pinfunction "GND_GND1") (pintype "bidirectional"))
      (node (ref "R21") (pin "1") (pinfunction "1_1") (pintype "passive"))
      (node (ref "R26") (pin "2") (pinfunction "2_2") (pintype "passive"))
      (node (ref "R27") (pin "2") (pinfunction "2_2") (pintype "passive"))
      (node (ref "R28") (pin "2") (pinfunction "2_2") (pintype "passive"))
      (node (ref "R29") (pin "2") (pinfunction "2_2") (pintype "passive"))
      (node (ref "R36") (pin "2") (pinfunction "2_2") (pintype "passive"))
      (node (ref "R6") (pin "2") (pinfunction "2_2") (pintype "passive"))
      (node (ref "RJ1") (pin "GND") (pinfunction "GND_GND") (pintype "bidirectional"))
      (node (ref "RJ1") (pin "SHIELD0") (pinfunction "SHIELD0_SHIELD0") (pintype "bidirectional"))
      (node (ref "RJ1") (pin "SHIELD1") (pinfunction "SHIELD1_SHIELD1") (pintype "bidirectional"))
      (node (ref "SV1") (pin "29") (pinfunction "29_29") (pintype "passive"))
      (node (ref "SV1") (pin "30") (pinfunction "30_30") (pintype "passive"))
      (node (ref "U$1") (pin "2") (pinfunction "GND_2") (pintype "power_in"))
      (node (ref "U$2") (pin "4") (pinfunction "VSS_4") (pintype "bidirectional"))
      (node (ref "U$3") (pin "13") (pinfunction "VSS_13") (pintype "bidirectional"))
      (node (ref "U$3") (pin "31") (pinfunction "AVSS_31") (pintype "bidirectional"))
      (node (ref "U$3") (pin "36") (pinfunction "VSS_36") (pintype "bidirectional"))
      (node (ref "U$3") (pin "45") (pinfunction "VSS_45") (pintype "bidirectional"))
      (node (ref "U$3") (pin "53") (pinfunction "VSS_53") (pintype "bidirectional"))
      (node (ref "U$3") (pin "63") (pinfunction "VSS_63") (pintype "bidirectional"))
      (node (ref "U$3") (pin "75") (pinfunction "VSS_75") (pintype "bidirectional"))
      (node (ref "U$3") (pin "84") (pinfunction "VSS_84") (pintype "bidirectional"))
      (node (ref "U$3") (pin "92") (pinfunction "VSS_92") (pintype "bidirectional"))
      (node (ref "U$4") (pin "2") (pinfunction "GND_2") (pintype "power_in"))
      (node (ref "U$7") (pin "2") (pinfunction "GND_2") (pintype "power_in"))
      (node (ref "U1") (pin "6") (pinfunction "GND_6") (pintype "bidirectional"))
      (node (ref "U1") (pin "CD2") (pinfunction "SHIELD_CD2") (pintype "bidirectional"))
      (node (ref "U1") (pin "GND1") (pinfunction "SHIELD_GND1") (pintype "bidirectional"))
      (node (ref "U1") (pin "GND2") (pinfunction "SHIELD_GND2") (pintype "bidirectional"))
      (node (ref "U2") (pin "16") (pinfunction "DGND1_16") (pintype "power_in"))
      (node (ref "U2") (pin "20") (pinfunction "DGND2_20") (pintype "power_in"))
      (node (ref "U2") (pin "21") (pinfunction "DGND3_21") (pintype "power_in"))
      (node (ref "U2") (pin "22") (pinfunction "DGND4_22") (pintype "power_in"))
      (node (ref "U2") (pin "4") (pinfunction "DGND_4") (pintype "power_in"))
      (node (ref "X1") (pin "2") (pinfunction "S_2") (pintype "passive"))
      (node (ref "X3") (pin "4") (pinfunction "4_4") (pintype "passive"))
      (node (ref "X3") (pin "M1") (pinfunction "S1_M1") (pintype "passive"))
      (node (ref "X3") (pin "M2") (pinfunction "S2_M2") (pintype "passive"))
      (node (ref "Y3") (pin "2") (pinfunction "3_2") (pintype "passive"))
      (node (ref "Y3") (pin "4") (pinfunction "3_4") (pintype "passive"))
    )
    (net (code "20") (name "LED_ACT") (class "Default")
      (node (ref "IC4") (pin "26") (pinfunction "LED_ACTCOL_26") (pintype "bidirectional"))
      (node (ref "RJ1") (pin "G-") (pinfunction "G-_G-") (pintype "bidirectional"))
    )
    (net (code "21") (name "LED_LINK") (class "Default")
      (node (ref "IC4") (pin "28") (pinfunction "LED_LNK_28") (pintype "bidirectional"))
      (node (ref "RJ1") (pin "Y-") (pinfunction "Y-_Y-") (pintype "bidirectional"))
    )
    (net (code "22") (name "MCLR") (class "Default")
      (node (ref "JP2") (pin "1") (pinfunction "1_1") (pintype "passive"))
      (node (ref "R12") (pin "1") (pinfunction "1_1") (pintype "passive"))
      (node (ref "U$3") (pin "15") (pinfunction "MCLR_15") (pintype "bidirectional"))
    )
    (net (code "23") (name "MISO") (class "Default")
      (node (ref "R16") (pin "1") (pinfunction "1_1") (pintype "passive"))
      (node (ref "U$2") (pin "2") (pinfunction "SO_2") (pintype "bidirectional"))
      (node (ref "U$3") (pin "64") (pinfunction "EBIA9/RPF4/SDA5/PMA9/RF4_64") (pintype "bidirectional"))
      (node (ref "U1") (pin "7") (pinfunction "DO_7") (pintype "bidirectional"))
    )
    (net (code "24") (name "MOSI") (class "Default")
      (node (ref "U$2") (pin "5") (pinfunction "SI_5") (pintype "bidirectional"))
      (node (ref "U$3") (pin "47") (pinfunction "AN32/AETXD0/RPD14/RD14_47") (pintype "bidirectional"))
      (node (ref "U1") (pin "3") (pinfunction "DI_3") (pintype "bidirectional"))
    )
    (net (code "25") (name "Net-(C28-Pad1)") (class "Default")
      (node (ref "C28") (pin "1") (pinfunction "1_1") (pintype "passive"))
      (node (ref "R12") (pin "2") (pinfunction "2_2") (pintype "passive"))
      (node (ref "R9") (pin "1") (pinfunction "1_1") (pintype "passive"))
    )
    (net (code "26") (name "Net-(C36-Pad2)") (class "Default")
      (node (ref "C36") (pin "2") (pinfunction "2_2") (pintype "passive"))
      (node (ref "R23") (pin "1") (pinfunction "1_1") (pintype "passive"))
    )
    (net (code "27") (name "Net-(C37-Pad2)") (class "Default")
      (node (ref "C37") (pin "2") (pinfunction "2_2") (pintype "passive"))
      (node (ref "R24") (pin "1") (pinfunction "1_1") (pintype "passive"))
    )
    (net (code "28") (name "Net-(C39-Pad2)") (class "Default")
      (node (ref "C39") (pin "2") (pinfunction "2_2") (pintype "passive"))
      (node (ref "R22") (pin "1") (pinfunction "1_1") (pintype "passive"))
    )
    (net (code "29") (name "Net-(C43-Pad1)") (class "Default")
      (node (ref "C43") (pin "1") (pinfunction "1_1") (pintype "passive"))
      (node (ref "R31") (pin "1") (pinfunction "1_1") (pintype "passive"))
    )
    (net (code "30") (name "Net-(C43-Pad2)") (class "Default")
      (node (ref "C43") (pin "2") (pinfunction "2_2") (pintype "passive"))
      (node (ref "J1") (pin "TIP") (pinfunction "TIP_TIP") (pintype "bidirectional"))
      (node (ref "R34") (pin "1") (pinfunction "1_1") (pintype "passive"))
    )
    (net (code "31") (name "Net-(C44-Pad1)") (class "Default")
      (node (ref "C44") (pin "1") (pinfunction "1_1") (pintype "passive"))
      (node (ref "R32") (pin "1") (pinfunction "1_1") (pintype "passive"))
    )
    (net (code "32") (name "Net-(C44-Pad2)") (class "Default")
      (node (ref "C44") (pin "2") (pinfunction "2_2") (pintype "passive"))
      (node (ref "J1") (pin "RING1") (pinfunction "RING1_RING1") (pintype "bidirectional"))
      (node (ref "R33") (pin "1") (pinfunction "1_1") (pintype "passive"))
    )
    (net (code "33") (name "Net-(IC1-I{slash}O_1)") (class "Default")
      (node (ref "IC1") (pin "1") (pinfunction "I/O_1_1") (pintype "bidirectional"))
      (node (ref "X3") (pin "2") (pinfunction "2_2") (pintype "passive"))
    )
    (net (code "34") (name "Net-(IC1-I{slash}O_2)") (class "Default")
      (node (ref "IC1") (pin "3") (pinfunction "I/O_2_3") (pintype "bidirectional"))
      (node (ref "X3") (pin "3") (pinfunction "3_3") (pintype "passive"))
    )
    (net (code "35") (name "Net-(IC4-IP_PH_M)") (class "Default")
      (node (ref "IC4") (pin "20") (pinfunction "IP_PH_M_20") (pintype "input"))
      (node (ref "R10") (pin "1") (pinfunction "1_1") (pintype "passive"))
    )
    (net (code "36") (name "Net-(IC4-IP_PH_P)") (class "Default")
      (node (ref "IC4") (pin "21") (pinfunction "IP_PH_P_21") (pintype "input"))
      (node (ref "R7") (pin "1") (pinfunction "1_1") (pintype "passive"))
    )
    (net (code "37") (name "Net-(IC4-RX_DV)") (class "Default")
      (node (ref "IC4") (pin "39") (pinfunction "RX_DV_39") (pintype "bidirectional"))
      (node (ref "R20") (pin "2") (pinfunction "2_2") (pintype "passive"))
    )
    (net (code "38") (name "Net-(IC4-VREF)") (class "Default")
      (node (ref "IC4") (pin "24") (pinfunction "VREF_24") (pintype "bidirectional"))
      (node (ref "R6") (pin "1") (pinfunction "1_1") (pintype "passive"))
    )
    (net (code "39") (name "Net-(JP5-VCC)") (class "Default")
      (node (ref "F1") (pin "1") (pinfunction "1_1") (pintype "passive"))
      (node (ref "JP5") (pin "VBUS1") (pinfunction "VCC_VBUS1") (pintype "bidirectional"))
      (node (ref "X1") (pin "1") (pinfunction "S_1") (pintype "passive"))
    )
    (net (code "40") (name "Net-(R42-Pad2)") (class "Default")
      (node (ref "R42") (pin "2") (pinfunction "2_2") (pintype "passive"))
      (node (ref "RJ1") (pin "G+") (pinfunction "G+_G+") (pintype "bidirectional"))
    )
    (net (code "41") (name "Net-(R43-Pad1)") (class "Default")
      (node (ref "R43") (pin "1") (pinfunction "1_1") (pintype "passive"))
      (node (ref "RJ1") (pin "Y+") (pinfunction "Y+_Y+") (pintype "bidirectional"))
    )
    (net (code "42") (name "Net-(U2A-GBUF)") (class "Default")
      (node (ref "R23") (pin "2") (pinfunction "2_2") (pintype "passive"))
      (node (ref "U2") (pin "42") (pinfunction "GBUF_42") (pintype "bidirectional"))
    )
    (net (code "43") (name "Net-(U2A-GPIO0)") (class "Default")
      (node (ref "R26") (pin "1") (pinfunction "1_1") (pintype "passive"))
      (node (ref "U2") (pin "33") (pinfunction "GPIO0_33") (pintype "bidirectional"))
    )
    (net (code "44") (name "Net-(U2A-GPIO1)") (class "Default")
      (node (ref "R27") (pin "1") (pinfunction "1_1") (pintype "passive"))
      (node (ref "U2") (pin "34") (pinfunction "GPIO1_34") (pintype "bidirectional"))
    )
    (net (code "45") (name "Net-(U2A-GPIO2{slash}DCLK)") (class "Default")
      (node (ref "R28") (pin "1") (pinfunction "1_1") (pintype "passive"))
      (node (ref "U2") (pin "9") (pinfunction "GPIO2/DCLK_9") (pintype "bidirectional"))
    )
    (net (code "46") (name "Net-(U2A-GPIO3{slash}SDATA)") (class "Default")
      (node (ref "R29") (pin "1") (pinfunction "1_1") (pintype "passive"))
      (node (ref "U2") (pin "10") (pinfunction "GPIO3/SDATA_10") (pintype "bidirectional"))
    )
    (net (code "47") (name "Net-(U2A-LEFT)") (class "Default")
      (node (ref "R22") (pin "2") (pinfunction "2_2") (pintype "passive"))
      (node (ref "R31") (pin "2") (pinfunction "2_2") (pintype "passive"))
      (node (ref "U2") (pin "46") (pinfunction "LEFT_46") (pintype "bidirectional"))
    )
    (net (code "48") (name "Net-(U2A-RCAP)") (class "Default")
      (node (ref "R25") (pin "2") (pinfunction "2_2") (pintype "passive"))
      (node (ref "U2") (pin "44") (pinfunction "RCAP_44") (pintype "bidirectional"))
    )
    (net (code "49") (name "Net-(U2A-RIGHT)") (class "Default")
      (node (ref "R24") (pin "2") (pinfunction "2_2") (pintype "passive"))
      (node (ref "R32") (pin "2") (pinfunction "2_2") (pintype "passive"))
      (node (ref "U2") (pin "39") (pinfunction "RIGHT_39") (pintype "bidirectional"))
    )
    (net (code "50") (name "Net-(U2A-RX)") (class "Default")
      (node (ref "R30") (pin "1") (pinfunction "1_1") (pintype "passive"))
      (node (ref "U2") (pin "26") (pinfunction "RX_26") (pintype "bidirectional"))
    )
    (net (code "51") (name "Net-(U2A-XTALI)") (class "Default")
      (node (ref "C50") (pin "1") (pinfunction "1_1") (pintype "passive"))
      (node (ref "R35") (pin "2") (pinfunction "2_2") (pintype "passive"))
      (node (ref "U2") (pin "18") (pinfunction "XTALI_18") (pintype "bidirectional"))
      (node (ref "Y3") (pin "1") (pinfunction "2_1") (pintype "passive"))
    )
    (net (code "52") (name "Net-(U2A-XTALO)") (class "Default")
      (node (ref "C49") (pin "1") (pinfunction "1_1") (pintype "passive"))
      (node (ref "R35") (pin "1") (pinfunction "1_1") (pintype "passive"))
      (node (ref "U2") (pin "17") (pinfunction "XTALO_17") (pintype "bidirectional"))
      (node (ref "Y3") (pin "3") (pinfunction "1_3") (pintype "passive"))
    )
    (net (code "53") (name "PGEC") (class "Default")
      (node (ref "JP2") (pin "5") (pinfunction "5_5") (pintype "passive"))
      (node (ref "U$3") (pin "24") (pinfunction "PGEC1/AN1/RPB1/RB1_24") (pintype "bidirectional"))
    )
    (net (code "54") (name "PGED") (class "Default")
      (node (ref "JP2") (pin "4") (pinfunction "4_4") (pintype "passive"))
      (node (ref "U$3") (pin "25") (pinfunction "PGED1/AN0/RPB0/RB0_25") (pintype "bidirectional"))
    )
    (net (code "55") (name "PH0") (class "Default")
      (node (ref "U$1") (pin "3") (pinfunction "OUT_3") (pintype "output"))
      (node (ref "U$3") (pin "49") (pinfunction "OSC1/CLKI/RC12_49") (pintype "bidirectional"))
    )
    (net (code "56") (name "RA2") (class "Default")
      (node (ref "SV1") (pin "4") (pinfunction "4_4") (pintype "passive"))
      (node (ref "U$3") (pin "59") (pinfunction "EBICS0/SCL2/RA2_59") (pintype "bidirectional"))
    )
    (net (code "57") (name "RA3") (class "Default")
      (node (ref "SV1") (pin "3") (pinfunction "3_3") (pintype "passive"))
      (node (ref "U$3") (pin "60") (pinfunction "EBIRDY1/SDA2/RA3_60") (pintype "bidirectional"))
    )
    (net (code "58") (name "RA4") (class "Default")
      (node (ref "SV1") (pin "6") (pinfunction "6_6") (pintype "passive"))
      (node (ref "U$3") (pin "61") (pinfunction "EBIA14/PMCS1/PMA14/RA4_61") (pintype "bidirectional"))
    )
    (net (code "59") (name "RA5") (class "Default")
      (node (ref "SV1") (pin "28") (pinfunction "28_28") (pintype "passive"))
      (node (ref "U$3") (pin "2") (pinfunction "EBIA5/AN34/PMA5/RA5_2") (pintype "bidirectional"))
    )
    (net (code "60") (name "RA6") (class "Default")
      (node (ref "SV1") (pin "15") (pinfunction "15_15") (pintype "passive"))
      (node (ref "U$3") (pin "89") (pinfunction "TRCLK/SQICLK/RA6_89") (pintype "bidirectional"))
    )
    (net (code "61") (name "RA7") (class "Default")
      (node (ref "SV1") (pin "18") (pinfunction "18_18") (pintype "passive"))
      (node (ref "U$3") (pin "90") (pinfunction "TRD3/SQID3/RA7_90") (pintype "bidirectional"))
    )
    (net (code "62") (name "RA14") (class "Default")
      (node (ref "SV1") (pin "5") (pinfunction "5_5") (pintype "passive"))
      (node (ref "U$3") (pin "66") (pinfunction "AETXCLK/RPA14/SCL1/RA14_66") (pintype "bidirectional"))
    )
    (net (code "63") (name "RD1") (class "Default")
      (node (ref "SV1") (pin "7") (pinfunction "7_7") (pintype "passive"))
      (node (ref "U$3") (pin "76") (pinfunction "RPD1/SCK1/RD1_76") (pintype "bidirectional"))
    )
    (net (code "64") (name "RD3") (class "Default")
      (node (ref "SV1") (pin "10") (pinfunction "10_10") (pintype "passive"))
      (node (ref "U$3") (pin "78") (pinfunction "EBID15/ETXCLK/RPD3/PMD15/RD3_78") (pintype "bidirectional"))
    )
    (net (code "65") (name "RD4") (class "Default")
      (node (ref "SV1") (pin "11") (pinfunction "11_11") (pintype "passive"))
      (node (ref "U$3") (pin "81") (pinfunction "SQICS0/RPD4/RD4_81") (pintype "bidirectional"))
    )
    (net (code "66") (name "RD5") (class "Default")
      (node (ref "SV1") (pin "14") (pinfunction "14_14") (pintype "passive"))
      (node (ref "U$3") (pin "82") (pinfunction "SQICS1/RPD5/RD5_82") (pintype "bidirectional"))
    )
    (net (code "67") (name "RD9") (class "Default")
      (node (ref "SV1") (pin "8") (pinfunction "8_8") (pintype "passive"))
      (node (ref "U$3") (pin "68") (pinfunction "EBIA15/RPD9/PMCS2/PMA15/RD9_68") (pintype "bidirectional"))
    )
    (net (code "68") (name "RD12") (class "Default")
      (node (ref "SV1") (pin "9") (pinfunction "9_9") (pintype "passive"))
      (node (ref "U$3") (pin "79") (pinfunction "EBID12/ETXD2/RPD12/PMD12/RD12_79") (pintype "bidirectional"))
    )
    (net (code "69") (name "RD13") (class "Default")
      (node (ref "SV1") (pin "12") (pinfunction "12_12") (pintype "passive"))
      (node (ref "U$3") (pin "80") (pinfunction "EBID13/ETXD3/PMD13/RD13_80") (pintype "bidirectional"))
    )
    (net (code "70") (name "RD_N") (class "Default")
      (node (ref "IC4") (pin "13") (pinfunction "TPRDM_13") (pintype "bidirectional"))
      (node (ref "R5") (pin "1") (pinfunction "1_1") (pintype "passive"))
      (node (ref "RJ1") (pin "RD-") (pinfunction "RD-_RD-") (pintype "bidirectional"))
    )
    (net (code "71") (name "RD_P") (class "Default")
      (node (ref "IC4") (pin "14") (pinfunction "TPRDP_14") (pintype "bidirectional"))
      (node (ref "R4") (pin "1") (pinfunction "1_1") (pintype "passive"))
      (node (ref "RJ1") (pin "RD+") (pinfunction "RD+_RD+") (pintype "bidirectional"))
    )
    (net (code "72") (name "RE0") (class "Default")
      (node (ref "SV1") (pin "17") (pinfunction "17_17") (pintype "passive"))
      (node (ref "U$3") (pin "91") (pinfunction "EBID0/PMD0/RE0_91") (pintype "bidirectional"))
    )
    (net (code "73") (name "RE1") (class "Default")
      (node (ref "SV1") (pin "20") (pinfunction "20_20") (pintype "passive"))
      (node (ref "U$3") (pin "94") (pinfunction "EBID1/PMD1/RE1_94") (pintype "bidirectional"))
    )
    (net (code "74") (name "RE2") (class "Default")
      (node (ref "SV1") (pin "24") (pinfunction "24_24") (pintype "passive"))
      (node (ref "U$3") (pin "98") (pinfunction "EBID2/PMD2/RE2_98") (pintype "bidirectional"))
    )
    (net (code "75") (name "RE3") (class "Default")
      (node (ref "SV1") (pin "23") (pinfunction "23_23") (pintype "passive"))
      (node (ref "U$3") (pin "99") (pinfunction "EBID3/RPE3/PMD3/RE3_99") (pintype "bidirectional"))
    )
    (net (code "76") (name "RE4") (class "Default")
      (node (ref "SV1") (pin "26") (pinfunction "26_26") (pintype "passive"))
      (node (ref "U$3") (pin "100") (pinfunction "EBID4/AN18/PMD4/RE4_100") (pintype "bidirectional"))
    )
    (net (code "77") (name "RE5") (class "Default")
      (node (ref "SV1") (pin "27") (pinfunction "27_27") (pintype "passive"))
      (node (ref "U$3") (pin "3") (pinfunction "EBID5/AN17/RPE5/PMD5/RE5_3") (pintype "bidirectional"))
    )
    (net (code "78") (name "REG_OUT") (class "Default")
      (node (ref "C18") (pin "1") (pinfunction "1_1") (pintype "passive"))
      (node (ref "C19") (pin "1") (pinfunction "1_1") (pintype "passive"))
      (node (ref "C24") (pin "1") (pinfunction "1_1") (pintype "passive"))
      (node (ref "C32") (pin "1") (pinfunction "1_1") (pintype "passive"))
      (node (ref "IC4") (pin "18") (pinfunction "ANA18VDD_18") (pintype "power_in"))
      (node (ref "IC4") (pin "23") (pinfunction "REG_OUT_23") (pintype "output"))
      (node (ref "IC4") (pin "37") (pinfunction "CORE_VDD_37") (pintype "power_in"))
    )
    (net (code "79") (name "RG0") (class "Default")
      (node (ref "SV1") (pin "16") (pinfunction "16_16") (pintype "passive"))
      (node (ref "U$3") (pin "88") (pinfunction "EBID8/RPG0/PMD8/RG0_88") (pintype "bidirectional"))
    )
    (net (code "80") (name "RG1") (class "Default")
      (node (ref "SV1") (pin "13") (pinfunction "13_13") (pintype "passive"))
      (node (ref "U$3") (pin "87") (pinfunction "EBID9/ETXERR/RPG1/PMD9/RG1_87") (pintype "bidirectional"))
    )
    (net (code "81") (name "RG12") (class "Default")
      (node (ref "SV1") (pin "22") (pinfunction "22_22") (pintype "passive"))
      (node (ref "U$3") (pin "96") (pinfunction "TRD1/SQID1/RG12_96") (pintype "bidirectional"))
    )
    (net (code "82") (name "RG13") (class "Default")
      (node (ref "SV1") (pin "21") (pinfunction "21_21") (pintype "passive"))
      (node (ref "U$3") (pin "97") (pinfunction "TRD0/SQID0/RG13_97") (pintype "bidirectional"))
    )
    (net (code "83") (name "RG14") (class "Default")
      (node (ref "SV1") (pin "19") (pinfunction "19_19") (pintype "passive"))
      (node (ref "U$3") (pin "95") (pinfunction "TRD2/SQID2/RG14_95") (pintype "bidirectional"))
    )
    (net (code "84") (name "RG15") (class "Default")
      (node (ref "SV1") (pin "25") (pinfunction "25_25") (pintype "passive"))
      (node (ref "U$3") (pin "1") (pinfunction "AN23/AERXERR/RG15_1") (pintype "bidirectional"))
    )
    (net (code "85") (name "SCK") (class "Default")
      (node (ref "U$2") (pin "6") (pinfunction "SCK_6") (pintype "bidirectional"))
      (node (ref "U$3") (pin "39") (pinfunction "TDI/EBIA18/AN30/RPF13/SCK5/RF13_39") (pintype "bidirectional"))
      (node (ref "U1") (pin "5") (pinfunction "SCK_5") (pintype "bidirectional"))
    )
    (net (code "86") (name "SCL") (class "Default")
      (node (ref "SV1") (pin "1") (pinfunction "1_1") (pintype "passive"))
      (node (ref "U$3") (pin "58") (pinfunction "EBIRDY2/RPF8/SCL3/RF8_58") (pintype "bidirectional"))
    )
    (net (code "87") (name "SDA") (class "Default")
      (node (ref "SV1") (pin "2") (pinfunction "2_2") (pintype "passive"))
      (node (ref "U$3") (pin "57") (pinfunction "EBIRDY3/RPF2/SDA3/RF2_57") (pintype "bidirectional"))
    )
    (net (code "88") (name "SD_CS") (class "Default")
      (node (ref "R11") (pin "1") (pinfunction "1_1") (pintype "passive"))
      (node (ref "U$3") (pin "48") (pinfunction "AN33/AETXD1/RPD15/SCK6/RD15_48") (pintype "bidirectional"))
      (node (ref "U1") (pin "2") (pinfunction "CS_2") (pintype "bidirectional"))
    )
    (net (code "89") (name "SD_PRESENT") (class "Default")
      (node (ref "R8") (pin "1") (pinfunction "1_1") (pintype "passive"))
      (node (ref "U$3") (pin "56") (pinfunction "RPF3/USBID/RF3_56") (pintype "bidirectional"))
      (node (ref "U1") (pin "CD1") (pinfunction "SHIELD_CD1") (pintype "bidirectional"))
    )
    (net (code "90") (name "SOSCI") (class "Default")
      (node (ref "U$3") (pin "72") (pinfunction "SOSCI/RPC13/RC13_72") (pintype "bidirectional"))
      (node (ref "U$4") (pin "3") (pinfunction "OUT_3") (pintype "output"))
    )
    (net (code "91") (name "SOSCO") (class "Default")
      (node (ref "U$3") (pin "73") (pinfunction "SOSCO/RPC14/T1CK/RC14_73") (pintype "bidirectional"))
    )
    (net (code "92") (name "TD_N") (class "Default")
      (node (ref "IC4") (pin "16") (pinfunction "TPTDM_16") (pintype "bidirectional"))
      (node (ref "R3") (pin "1") (pinfunction "1_1") (pintype "passive"))
      (node (ref "RJ1") (pin "TD-") (pinfunction "TD-_TD-") (pintype "bidirectional"))
    )
    (net (code "93") (name "TD_P") (class "Default")
      (node (ref "IC4") (pin "17") (pinfunction "TPTDP_17") (pintype "bidirectional"))
      (node (ref "R2") (pin "1") (pinfunction "1_1") (pintype "passive"))
      (node (ref "RJ1") (pin "TD+") (pinfunction "TD+_TD+") (pintype "bidirectional"))
    )
    (net (code "94") (name "U2_RX") (class "Default")
      (node (ref "JP3") (pin "3") (pinfunction "3_3") (pintype "passive"))
      (node (ref "U$3") (pin "32") (pinfunction "EBIA10/AN48/RPB8/PMA10/RB8_32") (pintype "bidirectional"))
    )
    (net (code "95") (name "U2_TX") (class "Default")
      (node (ref "JP3") (pin "2") (pinfunction "2_2") (pintype "passive"))
      (node (ref "U$3") (pin "26") (pinfunction "PGEC2/AN46/RPB6/RB6_26") (pintype "bidirectional"))
    )
    (net (code "96") (name "VBUS") (class "Default")
      (node (ref "C12") (pin "+") (pinfunction "+_+") (pintype "passive"))
      (node (ref "C13") (pin "1") (pinfunction "1_1") (pintype "passive"))
      (node (ref "C27") (pin "1") (pinfunction "1_1") (pintype "passive"))
      (node (ref "C30") (pin "+") (pinfunction "+_+") (pintype "passive"))
      (node (ref "C5") (pin "+") (pinfunction "+_+") (pintype "passive"))
      (node (ref "C52") (pin "+") (pinfunction "+_+") (pintype "passive"))
      (node (ref "C53") (pin "1") (pinfunction "1_1") (pintype "passive"))
      (node (ref "F1") (pin "2") (pinfunction "2_2") (pintype "passive"))
      (node (ref "IC1") (pin "5") (pinfunction "VBUS_5") (pintype "bidirectional"))
      (node (ref "IC2") (pin "3") (pinfunction "IN_3") (pintype "input"))
      (node (ref "IC5") (pin "3") (pinfunction "IN_3") (pintype "input"))
      (node (ref "SV1") (pin "31") (pinfunction "31_31") (pintype "passive"))
      (node (ref "SV1") (pin "32") (pinfunction "32_32") (pintype "passive"))
      (node (ref "U$3") (pin "51") (pinfunction "VBUS_51") (pintype "bidirectional"))
      (node (ref "X3") (pin "1") (pinfunction "1_1") (pintype "passive"))
    )
    (net (code "97") (name "VS_AGND") (class "Default")
      (node (ref "C33") (pin "2") (pinfunction "2_2") (pintype "passive"))
      (node (ref "C34") (pin "2") (pinfunction "2_2") (pintype "passive"))
      (node (ref "C35") (pin "2") (pinfunction "2_2") (pintype "passive"))
      (node (ref "C36") (pin "1") (pinfunction "1_1") (pintype "passive"))
      (node (ref "C37") (pin "1") (pinfunction "1_1") (pintype "passive"))
      (node (ref "C39") (pin "1") (pinfunction "1_1") (pintype "passive"))
      (node (ref "C58") (pin "2") (pinfunction "2_2") (pintype "passive"))
      (node (ref "J1") (pin "EARTH") (pinfunction "EARTH_EARTH") (pintype "bidirectional"))
      (node (ref "R21") (pin "2") (pinfunction "2_2") (pintype "passive"))
      (node (ref "R25") (pin "1") (pinfunction "1_1") (pintype "passive"))
      (node (ref "R33") (pin "2") (pinfunction "2_2") (pintype "passive"))
      (node (ref "R34") (pin "2") (pinfunction "2_2") (pintype "passive"))
      (node (ref "U2") (pin "37") (pinfunction "AGND_37") (pintype "power_in"))
      (node (ref "U2") (pin "40") (pinfunction "AGND1_40") (pintype "power_in"))
      (node (ref "U2") (pin "41") (pinfunction "AGND2_41") (pintype "power_in"))
      (node (ref "U2") (pin "47") (pinfunction "AGND3_47") (pintype "power_in"))
    )
    (net (code "98") (name "VS_AVDD") (class "Default")
      (node (ref "C33") (pin "1") (pinfunction "1_1") (pintype "passive"))
      (node (ref "C34") (pin "1") (pinfunction "1_1") (pintype "passive"))
      (node (ref "C35") (pin "1") (pinfunction "1_1") (pintype "passive"))
      (node (ref "C58") (pin "1") (pinfunction "1_1") (pintype "passive"))
      (node (ref "L1") (pin "1") (pinfunction "1_1") (pintype "passive"))
      (node (ref "U2") (pin "38") (pinfunction "AVDD_38") (pintype "power_in"))
      (node (ref "U2") (pin "43") (pinfunction "AVDD1_43") (pintype "power_in"))
      (node (ref "U2") (pin "45") (pinfunction "AVDD2_45") (pintype "power_in"))
    )
    (net (code "99") (name "VS_CVDD") (class "Default")
      (node (ref "C45") (pin "1") (pinfunction "1_1") (pintype "passive"))
      (node (ref "C46") (pin "1") (pinfunction "1_1") (pintype "passive"))
      (node (ref "C47") (pin "1") (pinfunction "1_1") (pintype "passive"))
      (node (ref "C48") (pin "1") (pinfunction "1_1") (pintype "passive"))
      (node (ref "C57") (pin "1") (pinfunction "1_1") (pintype "passive"))
      (node (ref "L2") (pin "1") (pinfunction "1_1") (pintype "passive"))
      (node (ref "U2") (pin "24") (pinfunction "CVDD2_24") (pintype "power_in"))
      (node (ref "U2") (pin "31") (pinfunction "CVDD3_31") (pintype "power_in"))
      (node (ref "U2") (pin "5") (pinfunction "CVDD_5") (pintype "power_in"))
      (node (ref "U2") (pin "7") (pinfunction "CVDD1_7") (pintype "power_in"))
    )
    (net (code "100") (name "VS_DREQ") (class "Default")
      (node (ref "U$3") (pin "6") (pinfunction "EBIA6/AN22/RPC1/PMA6/RC1_6") (pintype "bidirectional"))
      (node (ref "U2") (pin "8") (pinfunction "DREQ_8") (pintype "bidirectional"))
    )
    (net (code "101") (name "VS_MISO") (class "Default")
      (node (ref "U$3") (pin "65") (pinfunction "EBIA8/RPF5/SCL5/PMA8/RF5_65") (pintype "bidirectional"))
      (node (ref "U2") (pin "30") (pinfunction "SO_30") (pintype "bidirectional"))
    )
    (net (code "102") (name "VS_MOSI") (class "Default")
      (node (ref "U$3") (pin "67") (pinfunction "AETXEN/RPA15/SDA1/RA15_67") (pintype "bidirectional"))
      (node (ref "U2") (pin "29") (pinfunction "SI_29") (pintype "bidirectional"))
    )
    (net (code "103") (name "VS_SCK") (class "Default")
      (node (ref "U$3") (pin "69") (pinfunction "RPD10/SCK4/RD10_69") (pintype "bidirectional"))
      (node (ref "U2") (pin "28") (pinfunction "SCLK_28") (pintype "bidirectional"))
    )
    (net (code "104") (name "VS_XCS") (class "Default")
      (node (ref "U$3") (pin "5") (pinfunction "EBID7/AN15/PMD7/RE7_5") (pintype "bidirectional"))
      (node (ref "U2") (pin "23") (pinfunction "XCS_23") (pintype "bidirectional"))
    )
    (net (code "105") (name "VS_XDCS") (class "Default")
      (node (ref "U$3") (pin "4") (pinfunction "EBID6/AN16/PMD6/RE6_4") (pintype "bidirectional"))
      (node (ref "U2") (pin "13") (pinfunction "XDCS/BSYNC_13") (pintype "bidirectional"))
    )
    (net (code "106") (name "VS_XRST") (class "Default")
      (node (ref "R36") (pin "1") (pinfunction "1_1") (pintype "passive"))
      (node (ref "U$3") (pin "7") (pinfunction "EBIA12/AN21/RPC2/PMA12/RC2_7") (pintype "bidirectional"))
      (node (ref "U2") (pin "3") (pinfunction "XRESET_3") (pintype "bidirectional"))
    )
    (net (code "107") (name "_2V6") (class "Default")
      (node (ref "C51") (pin "+") (pinfunction "+_+") (pintype "passive"))
      (node (ref "C54") (pin "1") (pinfunction "1_1") (pintype "passive"))
      (node (ref "IC5") (pin "2") (pinfunction "OUT_2") (pintype "passive"))
      (node (ref "IC5") (pin "TAB") (pinfunction "OUT1_TAB") (pintype "passive"))
      (node (ref "L1") (pin "2") (pinfunction "2_2") (pintype "passive"))
      (node (ref "L2") (pin "2") (pinfunction "2_2") (pintype "passive"))
    )
    (net (code "108") (name "unconnected-(IC4-CLK2MAC-Pad25)") (class "Default")
      (node (ref "IC4") (pin "25") (pinfunction "CLK2MAC_25") (pintype "bidirectional"))
    )
    (net (code "109") (name "unconnected-(IC4-COL-Pad42)") (class "Default")
      (node (ref "IC4") (pin "42") (pinfunction "COL_42") (pintype "bidirectional"))
    )
    (net (code "110") (name "unconnected-(IC4-LED_SPD-Pad27)") (class "Default")
      (node (ref "IC4") (pin "27") (pinfunction "LED_SPD_27") (pintype "bidirectional"))
    )
    (net (code "111") (name "unconnected-(IC4-RXD_2-Pad45)") (class "Default")
      (node (ref "IC4") (pin "45") (pinfunction "RXD_2_45") (pintype "bidirectional"))
    )
    (net (code "112") (name "unconnected-(IC4-RXD_3-Pad46)") (class "Default")
      (node (ref "IC4") (pin "46") (pinfunction "RXD_3_46") (pintype "bidirectional"))
    )
    (net (code "113") (name "unconnected-(IC4-RX_CLK-Pad38)") (class "Default")
      (node (ref "IC4") (pin "38") (pinfunction "RX_CLK_38") (pintype "bidirectional"))
    )
    (net (code "114") (name "unconnected-(IC4-TCK-Pad8)") (class "Default")
      (node (ref "IC4") (pin "8") (pinfunction "TCK_8") (pintype "input"))
    )
    (net (code "115") (name "unconnected-(IC4-TDI-Pad12)") (class "Default")
      (node (ref "IC4") (pin "12") (pinfunction "TDI_12") (pintype "input"))
    )
    (net (code "116") (name "unconnected-(IC4-TDO-Pad9)") (class "Default")
      (node (ref "IC4") (pin "9") (pinfunction "TDO_9") (pintype "output"))
    )
    (net (code "117") (name "unconnected-(IC4-TMS-Pad10)") (class "Default")
      (node (ref "IC4") (pin "10") (pinfunction "TMS_10") (pintype "input"))
    )
    (net (code "118") (name "unconnected-(IC4-TRST_N-Pad11)") (class "Default")
      (node (ref "IC4") (pin "11") (pinfunction "TRST_N_11") (pintype "input"))
    )
    (net (code "119") (name "unconnected-(IC4-TXD_2-Pad5)") (class "Default")
      (node (ref "IC4") (pin "5") (pinfunction "TXD_2_5") (pintype "bidirectional"))
    )
    (net (code "120") (name "unconnected-(IC4-TX_CLK-Pad1)") (class "Default")
      (node (ref "IC4") (pin "1") (pinfunction "TX_CLK_1") (pintype "bidirectional"))
    )
    (net (code "121") (name "unconnected-(IC4-X2-Pad33)") (class "Default")
      (node (ref "IC4") (pin "33") (pinfunction "X2_33") (pintype "output"))
    )
    (net (code "122") (name "unconnected-(J1-PadRING2)") (class "Default")
      (node (ref "J1") (pin "RING2") (pinfunction "RING2_RING2") (pintype "bidirectional"))
    )
    (net (code "123") (name "unconnected-(JP2-Pad2)") (class "Default")
      (node (ref "JP2") (pin "2") (pinfunction "2_2") (pintype "passive"))
    )
    (net (code "124") (name "unconnected-(JP2-Pad6)") (class "Default")
      (node (ref "JP2") (pin "6") (pinfunction "6_6") (pintype "passive"))
    )
    (net (code "125") (name "unconnected-(JP5-D+-PadD+1)") (class "Default")
      (node (ref "JP5") (pin "D+1") (pinfunction "D+_D+1") (pintype "bidirectional"))
    )
    (net (code "126") (name "unconnected-(JP5-D--PadD-1)") (class "Default")
      (node (ref "JP5") (pin "D-1") (pinfunction "D-_D-1") (pintype "bidirectional"))
    )
    (net (code "127") (name "unconnected-(JP5-ID-PadID1)") (class "Default")
      (node (ref "JP5") (pin "ID1") (pinfunction "ID_ID1") (pintype "bidirectional"))
    )
    (net (code "128") (name "unconnected-(RJ1-PadNC)") (class "Default")
      (node (ref "RJ1") (pin "NC") (pinfunction "NC_NC") (pintype "bidirectional"))
    )
    (net (code "129") (name "unconnected-(U$1-TRI-Pad1)") (class "Default")
      (node (ref "U$1") (pin "1") (pinfunction "TRI_1") (pintype "input"))
    )
    (net (code "130") (name "unconnected-(U$3-AN2{slash}C2INB{slash}RPB2{slash}RB2-Pad23)") (class "Default")
      (node (ref "U$3") (pin "23") (pinfunction "AN2/C2INB/RPB2/RB2_23") (pintype "bidirectional"))
    )
    (net (code "131") (name "unconnected-(U$3-AN3{slash}C2INA{slash}RPB3{slash}RB3-Pad22)") (class "Default")
      (node (ref "U$3") (pin "22") (pinfunction "AN3/C2INA/RPB3/RB3_22") (pintype "bidirectional"))
    )
    (net (code "132") (name "unconnected-(U$3-AN4{slash}C1INB{slash}RB4-Pad21)") (class "Default")
      (node (ref "U$3") (pin "21") (pinfunction "AN4/C1INB/RB4_21") (pintype "bidirectional"))
    )
    (net (code "133") (name "unconnected-(U$3-AN14{slash}C1IND{slash}ECOL{slash}RPG6{slash}SCK2{slash}RG6-Pad10)") (class "Default")
      (node (ref "U$3") (pin "10") (pinfunction "AN14/C1IND/ECOL/RPG6/SCK2/RG6_10") (pintype "bidirectional"))
    )
    (net (code "134") (name "unconnected-(U$3-AN25{slash}AERXD0{slash}RPE8{slash}RE8-Pad18)") (class "Default")
      (node (ref "U$3") (pin "18") (pinfunction "AN25/AERXD0/RPE8/RE8_18") (pintype "bidirectional"))
    )
    (net (code "135") (name "unconnected-(U$3-AN26{slash}AERXD1{slash}RPE9{slash}RE9-Pad19)") (class "Default")
      (node (ref "U$3") (pin "19") (pinfunction "AN26/AERXD1/RPE9/RE9_19") (pintype "bidirectional"))
    )
    (net (code "136") (name "unconnected-(U$3-AN45{slash}C1INA{slash}RPB5{slash}RB5-Pad20)") (class "Default")
      (node (ref "U$3") (pin "20") (pinfunction "AN45/C1INA/RPB5/RB5_20") (pintype "bidirectional"))
    )
    (net (code "137") (name "unconnected-(U$3-EBIA0{slash}AN10{slash}ERXD3{slash}AETXD2{slash}RPB15{slash}OCFB{slash}PMA0{slash}RB15-Pad44)") (class "Default")
      (node (ref "U$3") (pin "44") (pinfunction "EBIA0/AN10/ERXD3/AETXD2/RPB15/OCFB/PMA0/RB15_44") (pintype "bidirectional"))
    )
    (net (code "138") (name "unconnected-(U$3-EBIA1{slash}AN9{slash}ERXD2{slash}AETXD3{slash}RPB14{slash}SCK3{slash}PMA1{slash}RB14-Pad43)") (class "Default")
      (node (ref "U$3") (pin "43") (pinfunction "EBIA1/AN9/ERXD2/AETXD3/RPB14/SCK3/PMA1/RB14_43") (pintype "bidirectional"))
    )
    (net (code "139") (name "unconnected-(U$3-EBIA4{slash}AN13{slash}C1INC{slash}ECRS{slash}RPG7{slash}SDA4{slash}PMA4{slash}RG7-Pad11)") (class "Default")
      (node (ref "U$3") (pin "11") (pinfunction "EBIA4/AN13/C1INC/ECRS/RPG7/SDA4/PMA4/RG7_11") (pintype "bidirectional"))
    )
    (net (code "140") (name "unconnected-(U$3-EBIA7{slash}AN49{slash}RPB9{slash}PMA7{slash}RB9-Pad33)") (class "Default")
      (node (ref "U$3") (pin "33") (pinfunction "EBIA7/AN49/RPB9/PMA7/RB9_33") (pintype "bidirectional"))
    )
    (net (code "141") (name "unconnected-(U$3-EBIOE{slash}AN19{slash}RPC4{slash}PMRD{slash}RC4-Pad9)") (class "Default")
      (node (ref "U$3") (pin "9") (pinfunction "EBIOE/AN19/RPC4/PMRD/RC4_9") (pintype "bidirectional"))
    )
    (net (code "142") (name "unconnected-(U$3-EBIWE{slash}AN20{slash}RPC3{slash}PMWR{slash}RC3-Pad8)") (class "Default")
      (node (ref "U$3") (pin "8") (pinfunction "EBIWE/AN20/RPC3/PMWR/RC3_8") (pintype "bidirectional"))
    )
    (net (code "143") (name "unconnected-(U$3-OSC2{slash}CLKO{slash}RC15-Pad50)") (class "Default")
      (node (ref "U$3") (pin "50") (pinfunction "OSC2/CLKO/RC15_50") (pintype "bidirectional"))
    )
    (net (code "144") (name "unconnected-(U$3-PGED2{slash}AN47{slash}RPB7{slash}RB7-Pad27)") (class "Default")
      (node (ref "U$3") (pin "27") (pinfunction "PGED2/AN47/RPB7/RB7_27") (pintype "bidirectional"))
    )
    (net (code "145") (name "unconnected-(U$3-TDO{slash}EBIA17{slash}AN31{slash}RPF12{slash}RF12-Pad40)") (class "Default")
      (node (ref "U$3") (pin "40") (pinfunction "TDO/EBIA17/AN31/RPF12/RF12_40") (pintype "bidirectional"))
    )
    (net (code "146") (name "unconnected-(U$3-TMS{slash}EBIA16{slash}AN24{slash}RA0-Pad17)") (class "Default")
      (node (ref "U$3") (pin "17") (pinfunction "TMS/EBIA16/AN24/RA0_17") (pintype "bidirectional"))
    )
    (net (code "147") (name "unconnected-(U$3-VREF+{slash}CVREF+{slash}AN28{slash}AERXD3{slash}RA10-Pad29)") (class "Default")
      (node (ref "U$3") (pin "29") (pinfunction "VREF+/CVREF+/AN28/AERXD3/RA10_29") (pintype "bidirectional"))
    )
    (net (code "148") (name "unconnected-(U$3-VREF-{slash}CVREF-{slash}AN27{slash}AERXD2{slash}RA9-Pad28)") (class "Default")
      (node (ref "U$3") (pin "28") (pinfunction "VREF-/CVREF-/AN27/AERXD2/RA9_28") (pintype "bidirectional"))
    )
    (net (code "149") (name "unconnected-(U$4-TRI-Pad1)") (class "Default")
      (node (ref "U$4") (pin "1") (pinfunction "TRI_1") (pintype "input"))
    )
    (net (code "150") (name "unconnected-(U$7-TRI-Pad1)") (class "Default")
      (node (ref "U$7") (pin "1") (pinfunction "TRI_1") (pintype "input"))
    )
    (net (code "151") (name "unconnected-(U1-NC-Pad1)") (class "Default")
      (node (ref "U1") (pin "1") (pinfunction "NC_1") (pintype "bidirectional"))
    )
    (net (code "152") (name "unconnected-(U1-RSV-Pad8)") (class "Default")
      (node (ref "U1") (pin "8") (pinfunction "RSV_8") (pintype "bidirectional"))
    )
    (net (code "153") (name "unconnected-(U2A-LINEIN-Pad48)") (class "Default")
      (node (ref "U2") (pin "48") (pinfunction "LINEIN_48") (pintype "bidirectional"))
    )
    (net (code "154") (name "unconnected-(U2A-MICN-Pad2)") (class "Default")
      (node (ref "U2") (pin "2") (pinfunction "MICN_2") (pintype "bidirectional"))
    )
    (net (code "155") (name "unconnected-(U2A-MICP-Pad1)") (class "Default")
      (node (ref "U2") (pin "1") (pinfunction "MICP_1") (pintype "bidirectional"))
    )
    (net (code "156") (name "unconnected-(U2A-TX-Pad27)") (class "Default")
      (node (ref "U2") (pin "27") (pinfunction "TX_27") (pintype "bidirectional"))
    )
    (net (code "157") (name "unconnected-(U2A-VCO-Pad15)") (class "Default")
      (node (ref "U2") (pin "15") (pinfunction "VCO_15") (pintype "bidirectional"))
    )
  )
)
